# BatteryBoardV2B.net
KiCad netlist of a schematic drawn in EAGLE
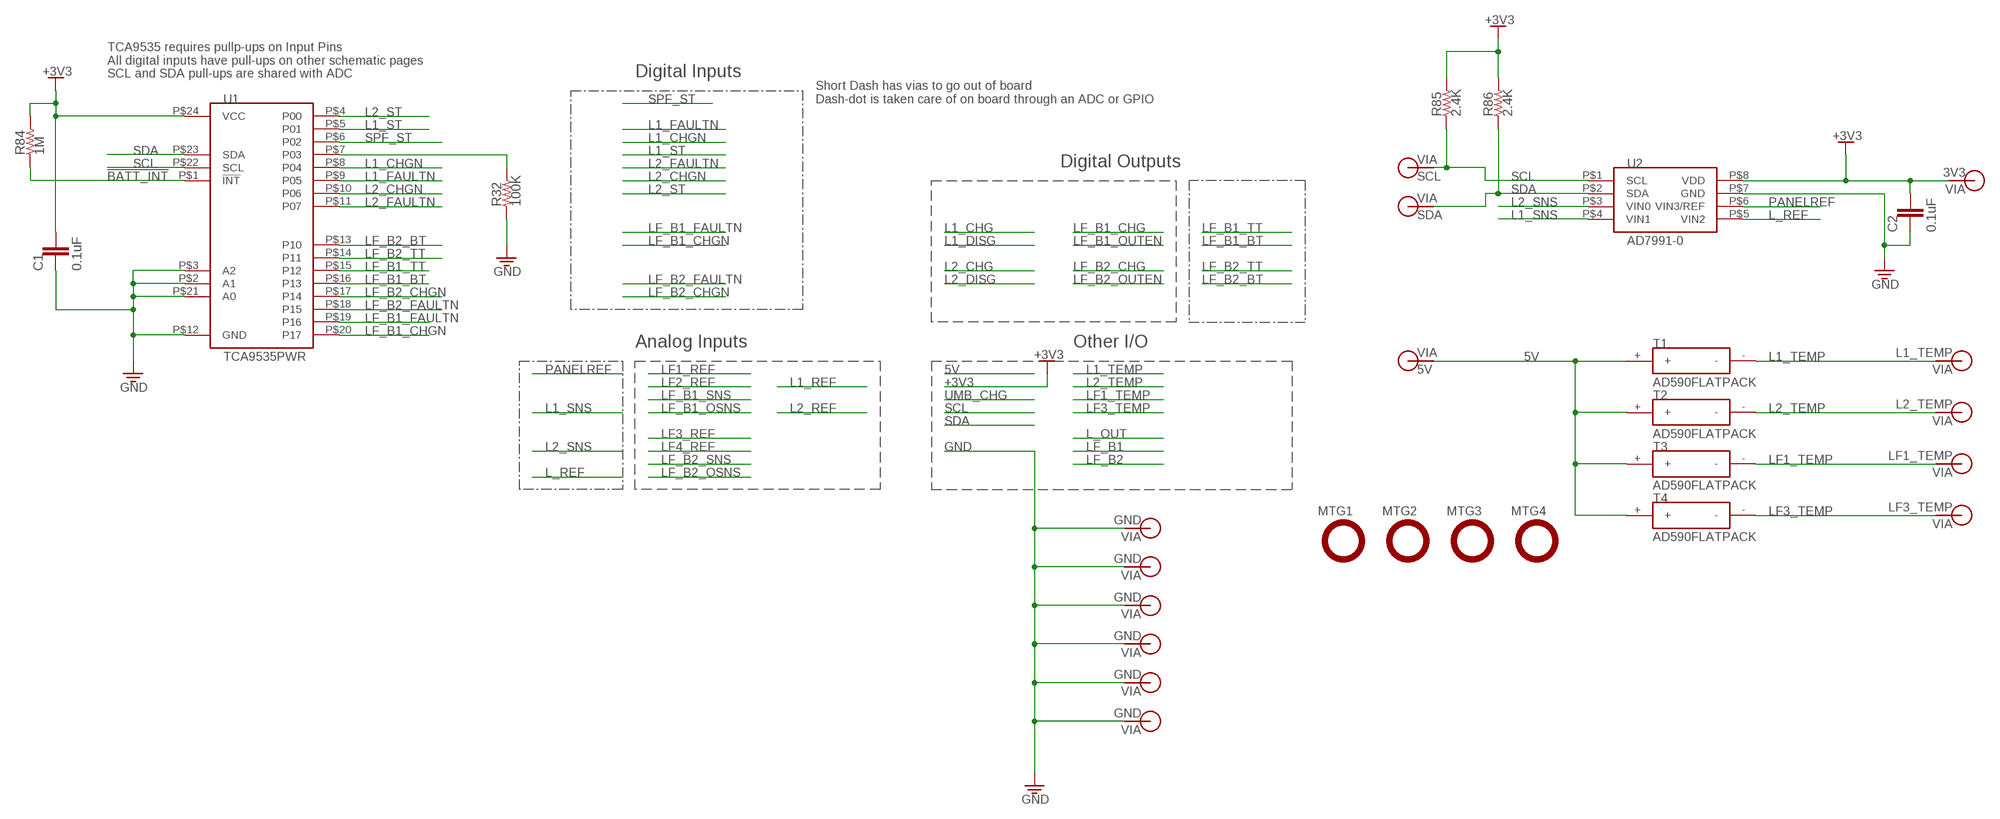
[diagram p0: schematic, sheet 1]
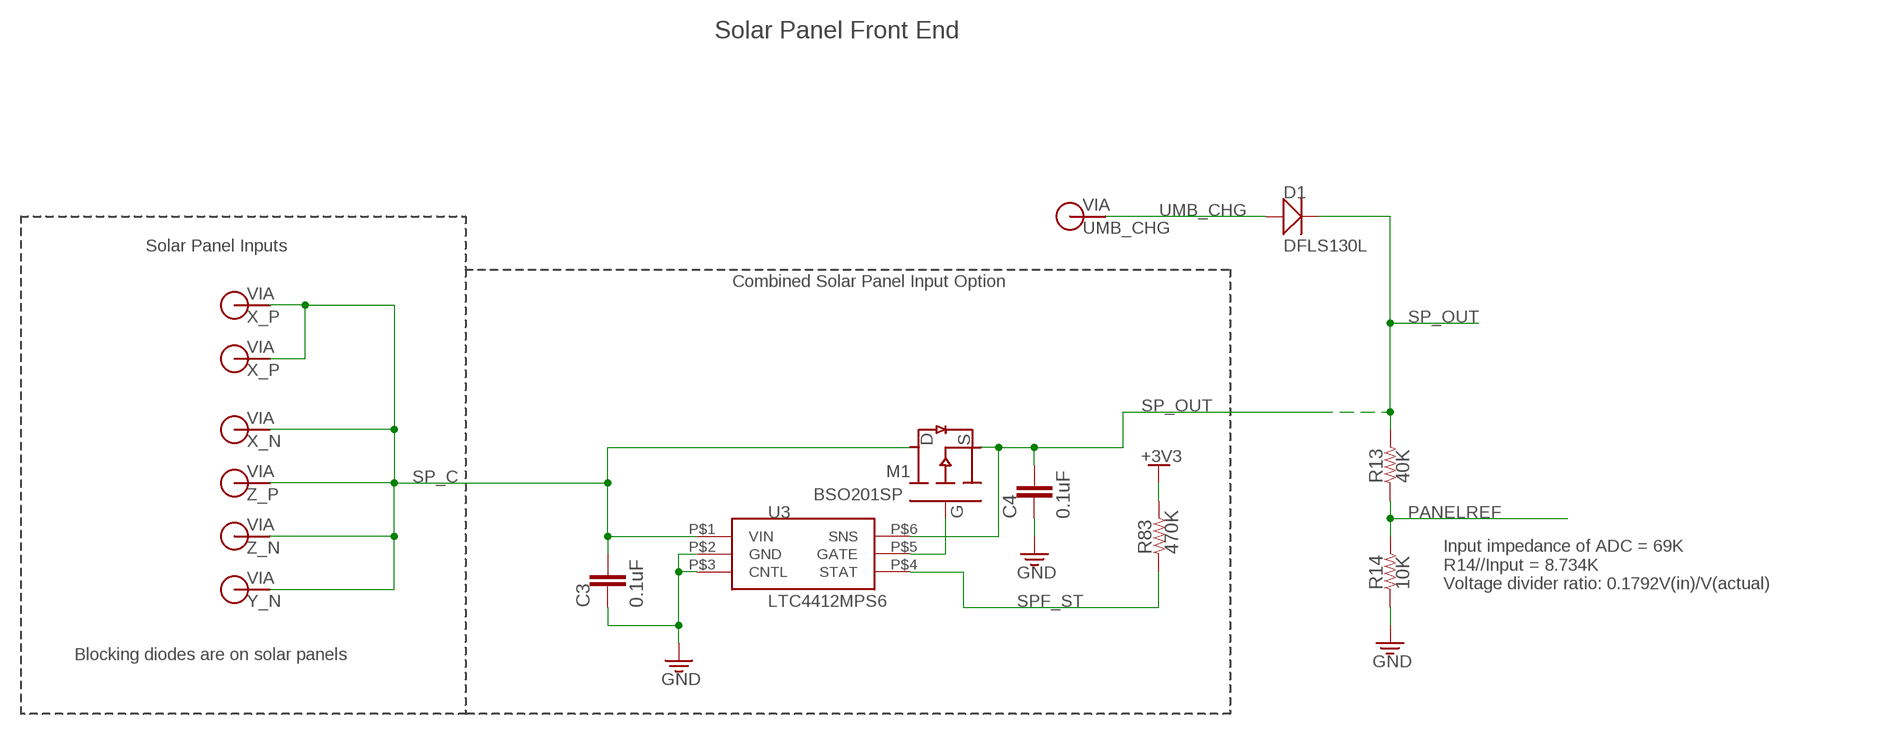
[diagram p1: schematic, sheet 2]
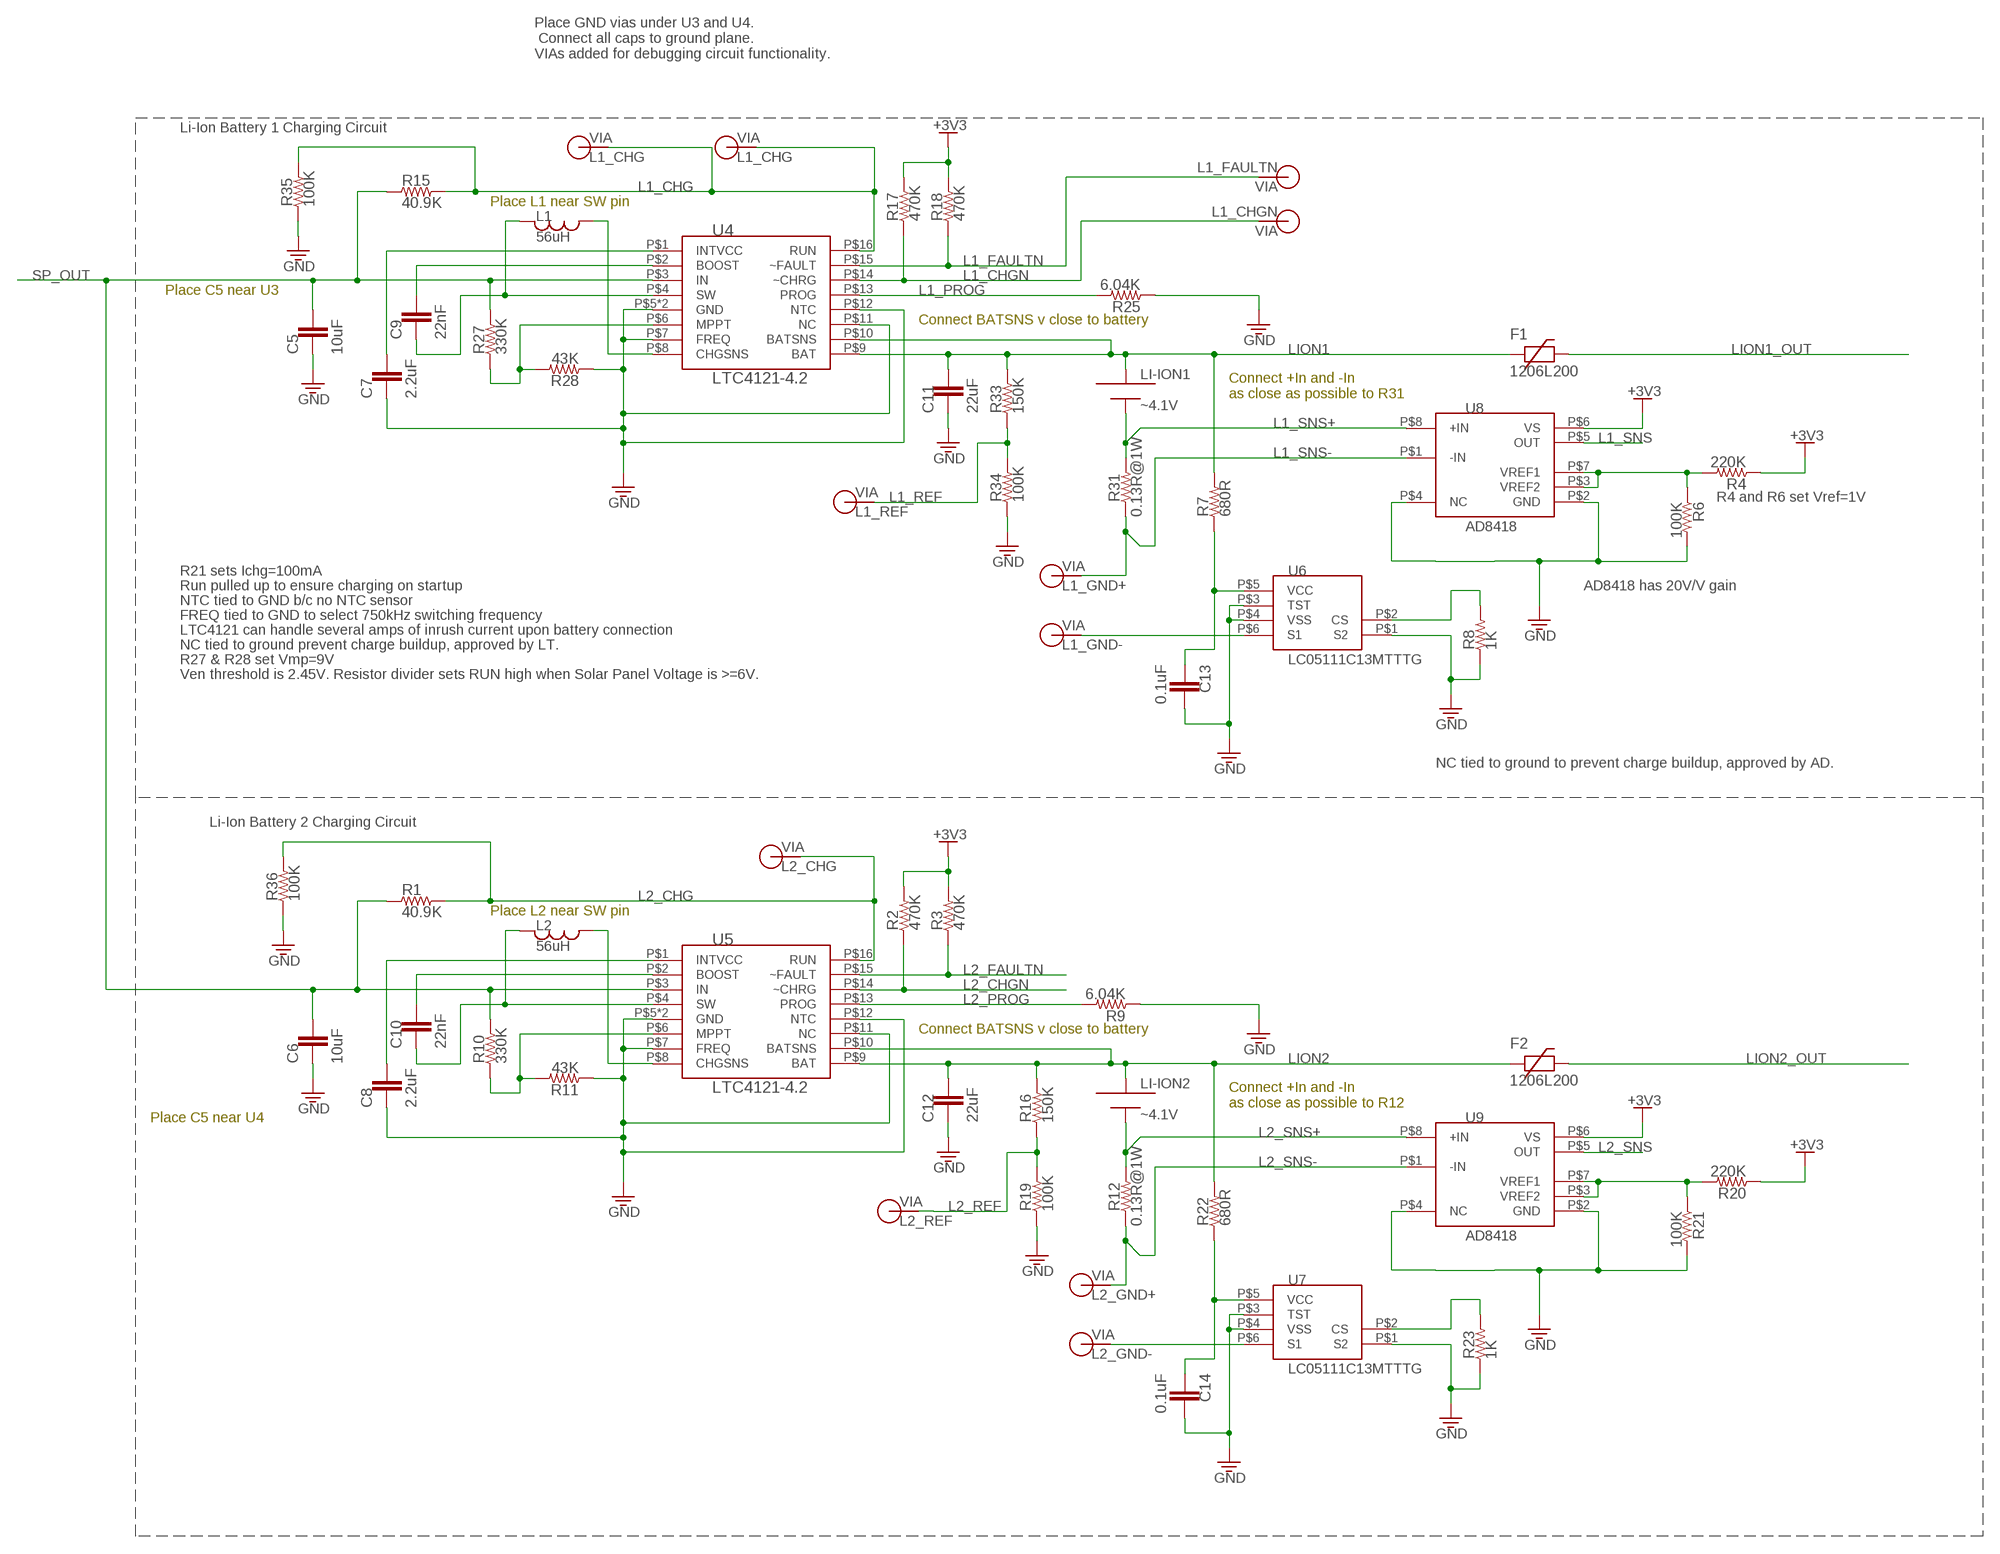
[diagram p2: schematic, sheet 3]
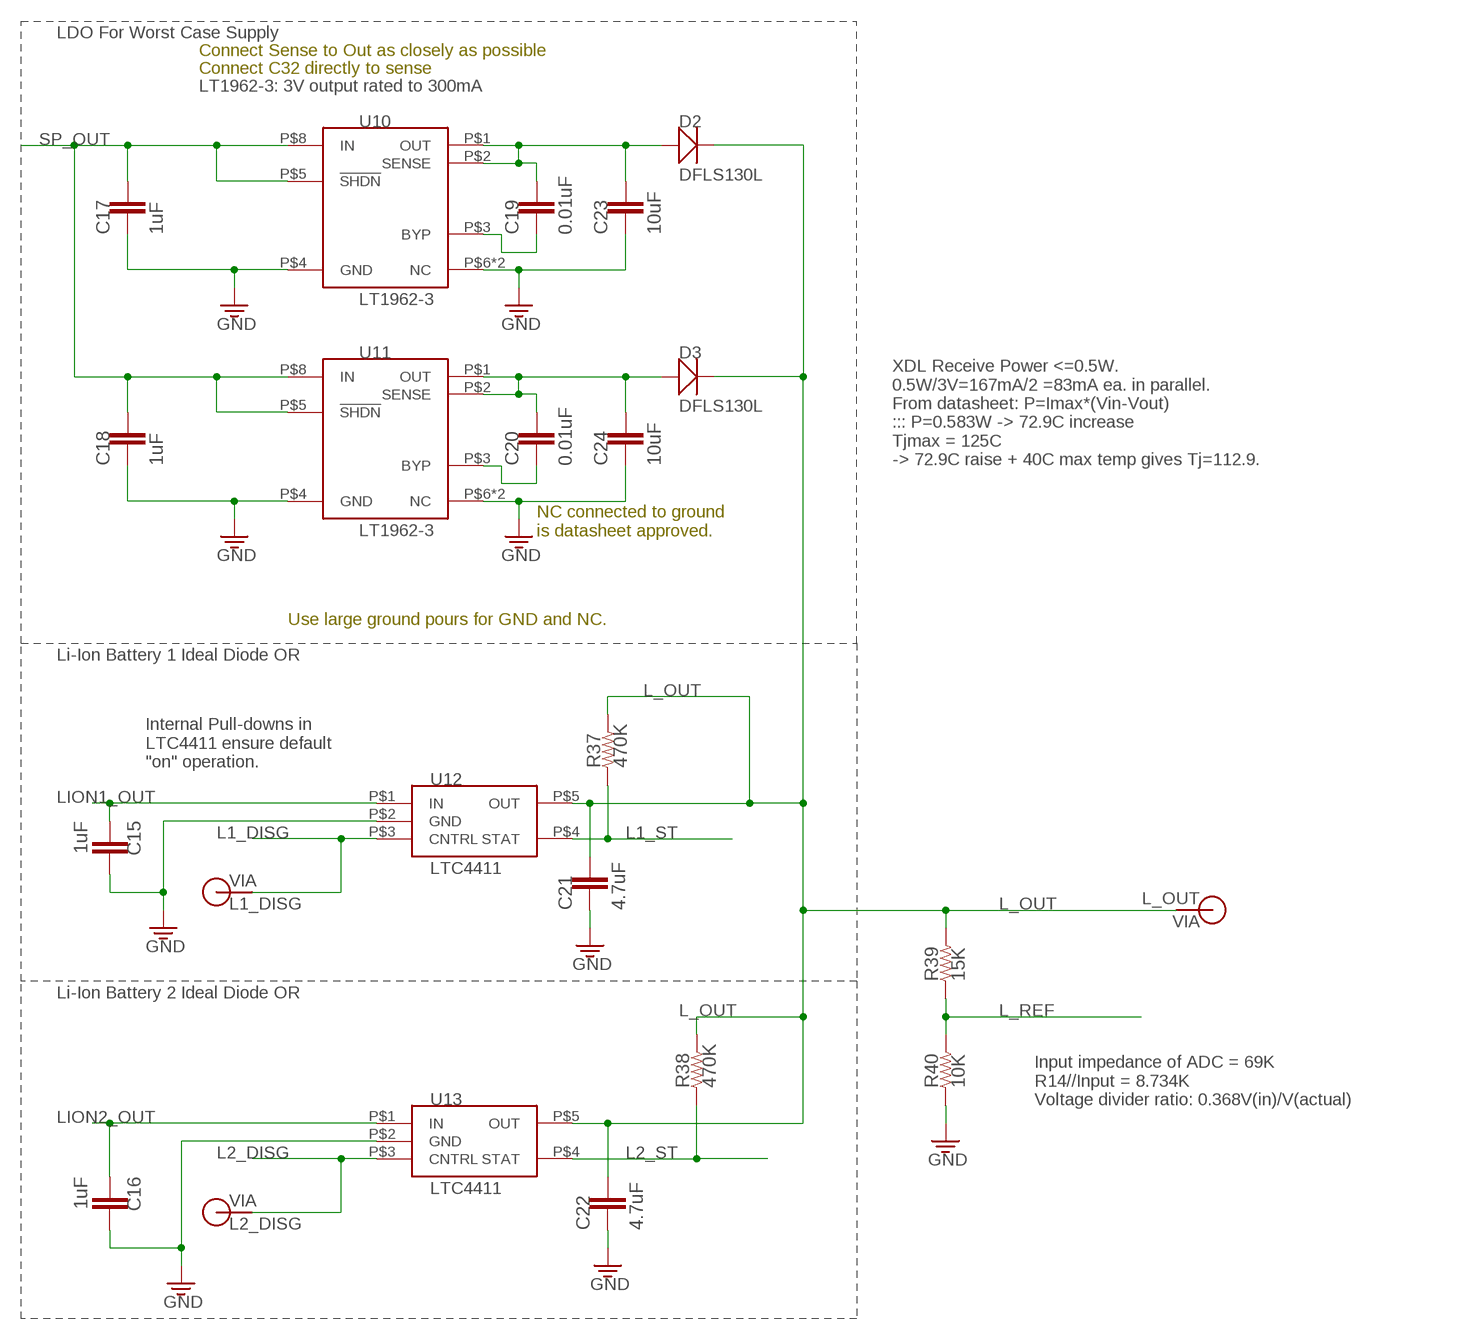
[diagram p3: schematic, sheet 4]
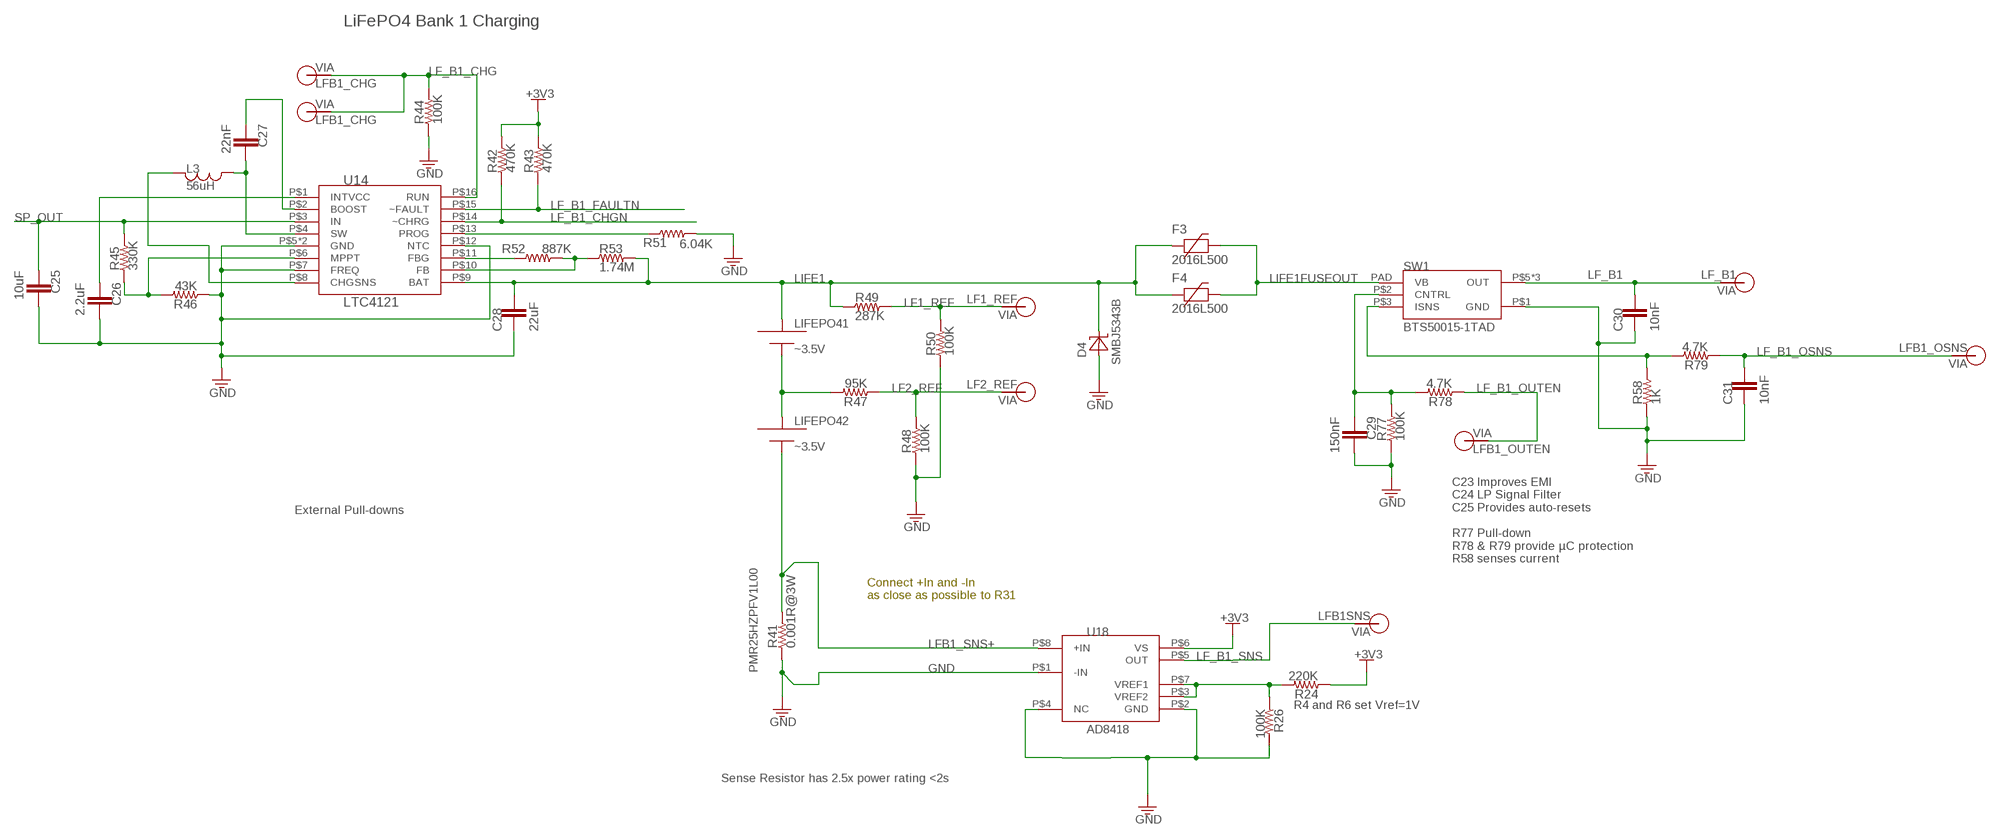
[diagram p4: schematic, sheet 5]
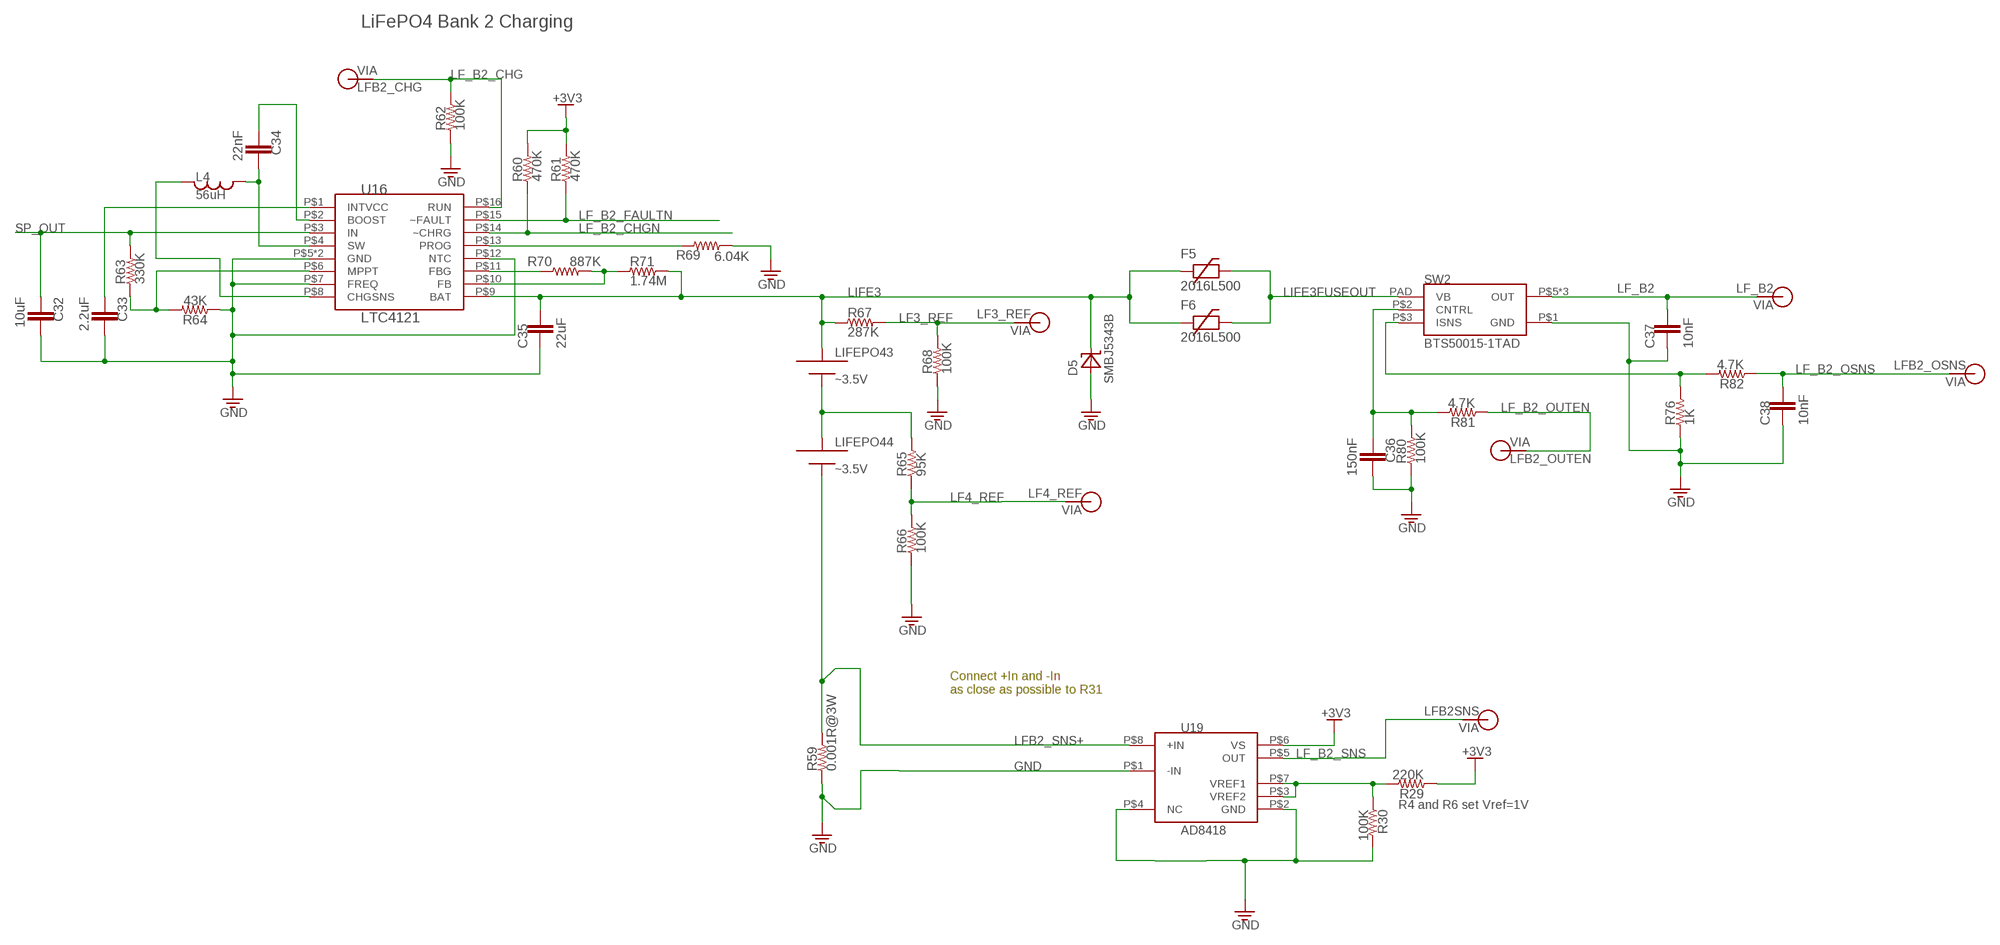
[diagram p5: schematic, sheet 6]

(export (version "E")
  (design (tool "Eeschema 10.0.6"))
  (components
    (comp (ref "C3")
      (value "0.1uF")
      (footprint "eagle-import:0805")
      (libsource (lib "eagle-import") (part "CAP0805"))
    )
    (comp (ref "C4")
      (value "0.1uF")
      (footprint "eagle-import:0805")
      (libsource (lib "eagle-import") (part "CAP0805"))
    )
    (comp (ref "D1")
      (value "DFLS130L")
      (footprint "eagle-import:PWRDI-123")
      (libsource (lib "eagle-import") (part "DFLS130L"))
    )
    (comp (ref "M1")
      (value "BSO201SP")
      (footprint "eagle-import:SO-8")
      (libsource (lib "eagle-import") (part "BSO201SP"))
    )
    (comp (ref "R13")
      (value "40K")
      (footprint "eagle-import:0805")
      (libsource (lib "eagle-import") (part "RES0805"))
    )
    (comp (ref "R14")
      (value "10K")
      (footprint "eagle-import:0805")
      (libsource (lib "eagle-import") (part "RES0805"))
    )
    (comp (ref "R83")
      (value "470K")
      (footprint "eagle-import:0805")
      (libsource (lib "eagle-import") (part "RES0805"))
    )
    (comp (ref "U3")
      (value "LTC4412MPS6")
      (footprint "eagle-import:TSOT23-6")
      (libsource (lib "eagle-import") (part "LTC4412"))
    )
    (comp (ref "V13")
      (value "X_P")
      (footprint "eagle-import:VIA-60MIL")
      (libsource (lib "eagle-import") (part "VIA-60MIL"))
    )
    (comp (ref "V14")
      (value "X_P")
      (footprint "eagle-import:VIA-60MIL-SQ")
      (libsource (lib "eagle-import") (part "VIA60MIL-SQ"))
    )
    (comp (ref "V15")
      (value "X_N")
      (footprint "eagle-import:VIA-60MIL")
      (libsource (lib "eagle-import") (part "VIA-60MIL"))
    )
    (comp (ref "V16")
      (value "Z_P")
      (footprint "eagle-import:VIA-60MIL")
      (libsource (lib "eagle-import") (part "VIA-60MIL"))
    )
    (comp (ref "V17")
      (value "Z_N")
      (footprint "eagle-import:VIA-60MIL")
      (libsource (lib "eagle-import") (part "VIA-60MIL"))
    )
    (comp (ref "V18")
      (value "Y_N")
      (footprint "eagle-import:VIA-60MIL")
      (libsource (lib "eagle-import") (part "VIA-60MIL"))
    )
    (comp (ref "V19")
      (value "UMB_CHG")
      (footprint "eagle-import:VIA-60MIL")
      (libsource (lib "eagle-import") (part "VIA-60MIL"))
    )
    (comp (ref "C1")
      (value "0.1uF")
      (footprint "eagle-import:0805")
      (libsource (lib "eagle-import") (part "CAP0805"))
    )
    (comp (ref "C2")
      (value "0.1uF")
      (footprint "eagle-import:0805")
      (libsource (lib "eagle-import") (part "CAP0805"))
    )
    (comp (ref "MTG1")
      (value "MTG-NPTH-#2-CLOSE")
      (footprint "eagle-import:#2-CLOSE-NPTH")
      (libsource (lib "eagle-import") (part "MTG-NPTH-#2-CLOSE"))
    )
    (comp (ref "MTG2")
      (value "MTG-NPTH-#2-CLOSE")
      (footprint "eagle-import:#2-CLOSE-NPTH")
      (libsource (lib "eagle-import") (part "MTG-NPTH-#2-CLOSE"))
    )
    (comp (ref "MTG3")
      (value "MTG-NPTH-#2-CLOSE")
      (footprint "eagle-import:#2-CLOSE-NPTH")
      (libsource (lib "eagle-import") (part "MTG-NPTH-#2-CLOSE"))
    )
    (comp (ref "MTG4")
      (value "MTG-NPTH-#2-CLOSE")
      (footprint "eagle-import:#2-CLOSE-NPTH")
      (libsource (lib "eagle-import") (part "MTG-NPTH-#2-CLOSE"))
    )
    (comp (ref "R32")
      (value "100K")
      (footprint "eagle-import:0805")
      (libsource (lib "eagle-import") (part "RES0805"))
    )
    (comp (ref "R84")
      (value "1M")
      (footprint "eagle-import:0805")
      (libsource (lib "eagle-import") (part "RES0805"))
    )
    (comp (ref "R85")
      (value "2.4K")
      (footprint "eagle-import:0805")
      (libsource (lib "eagle-import") (part "RES0805"))
    )
    (comp (ref "R86")
      (value "2.4K")
      (footprint "eagle-import:0805")
      (libsource (lib "eagle-import") (part "RES0805"))
    )
    (comp (ref "T1")
      (value "AD590FLATPACK")
      (footprint "eagle-import:FLATPACK")
      (libsource (lib "eagle-import") (part "AD590FLATPACK"))
    )
    (comp (ref "T2")
      (value "AD590FLATPACK")
      (footprint "eagle-import:FLATPACK")
      (libsource (lib "eagle-import") (part "AD590FLATPACK"))
    )
    (comp (ref "T3")
      (value "AD590FLATPACK")
      (footprint "eagle-import:FLATPACK")
      (libsource (lib "eagle-import") (part "AD590FLATPACK"))
    )
    (comp (ref "T4")
      (value "AD590FLATPACK")
      (footprint "eagle-import:FLATPACK")
      (libsource (lib "eagle-import") (part "AD590FLATPACK"))
    )
    (comp (ref "U1")
      (value "TCA9535PWR")
      (footprint "eagle-import:TSSOP-24")
      (libsource (lib "eagle-import") (part "TCA9535PWR"))
    )
    (comp (ref "U2")
      (value "AD7991-0")
      (footprint "eagle-import:SOT-23-8")
      (libsource (lib "eagle-import") (part "AD7991-0"))
    )
    (comp (ref "V1")
      (value "GND")
      (footprint "eagle-import:VIA-120MIL")
      (libsource (lib "eagle-import") (part "VIA-120MIL"))
    )
    (comp (ref "V2")
      (value "GND")
      (footprint "eagle-import:VIA-120MIL")
      (libsource (lib "eagle-import") (part "VIA-120MIL"))
    )
    (comp (ref "V3")
      (value "GND")
      (footprint "eagle-import:VIA-60MIL-SQ")
      (libsource (lib "eagle-import") (part "VIA60MIL-SQ"))
    )
    (comp (ref "V4")
      (value "GND")
      (footprint "eagle-import:VIA-120MIL")
      (libsource (lib "eagle-import") (part "VIA-120MIL"))
    )
    (comp (ref "V5")
      (value "SCL")
      (footprint "eagle-import:VIA-60MIL")
      (libsource (lib "eagle-import") (part "VIA-60MIL"))
    )
    (comp (ref "V6")
      (value "SDA")
      (footprint "eagle-import:VIA-60MIL")
      (libsource (lib "eagle-import") (part "VIA-60MIL"))
    )
    (comp (ref "V7")
      (value "5V")
      (footprint "eagle-import:VIA-60MIL")
      (libsource (lib "eagle-import") (part "VIA-60MIL"))
    )
    (comp (ref "V8")
      (value "L1_TEMP")
      (footprint "eagle-import:VIA-60MIL")
      (libsource (lib "eagle-import") (part "VIA-60MIL"))
    )
    (comp (ref "V9")
      (value "L2_TEMP")
      (footprint "eagle-import:VIA-60MIL")
      (libsource (lib "eagle-import") (part "VIA-60MIL"))
    )
    (comp (ref "V10")
      (value "LF1_TEMP")
      (footprint "eagle-import:VIA-60MIL")
      (libsource (lib "eagle-import") (part "VIA-60MIL"))
    )
    (comp (ref "V11")
      (value "LF3_TEMP")
      (footprint "eagle-import:VIA-60MIL")
      (libsource (lib "eagle-import") (part "VIA-60MIL"))
    )
    (comp (ref "V12")
      (value "3V3")
      (footprint "eagle-import:VIA-60MIL")
      (libsource (lib "eagle-import") (part "VIA-60MIL"))
    )
    (comp (ref "V28")
      (value "GND")
      (footprint "eagle-import:VIA-60MIL-SQ")
      (libsource (lib "eagle-import") (part "VIA60MIL-SQ"))
    )
    (comp (ref "V36")
      (value "GND")
      (footprint "eagle-import:VIA-60MIL-SQ")
      (libsource (lib "eagle-import") (part "VIA60MIL-SQ"))
    )
    (comp (ref "C5")
      (value "10uF")
      (footprint "eagle-import:0805")
      (libsource (lib "eagle-import") (part "CAP0805"))
    )
    (comp (ref "C6")
      (value "10uF")
      (footprint "eagle-import:0805")
      (libsource (lib "eagle-import") (part "CAP0805"))
    )
    (comp (ref "C7")
      (value "2.2uF")
      (footprint "eagle-import:0805")
      (libsource (lib "eagle-import") (part "CAP0805"))
    )
    (comp (ref "C8")
      (value "2.2uF")
      (footprint "eagle-import:0805")
      (libsource (lib "eagle-import") (part "CAP0805"))
    )
    (comp (ref "C9")
      (value "22nF")
      (footprint "eagle-import:0805")
      (libsource (lib "eagle-import") (part "CAP0805"))
    )
    (comp (ref "C10")
      (value "22nF")
      (footprint "eagle-import:0805")
      (libsource (lib "eagle-import") (part "CAP0805"))
    )
    (comp (ref "C11")
      (value "22uF")
      (footprint "eagle-import:0805")
      (libsource (lib "eagle-import") (part "CAP0805"))
    )
    (comp (ref "C12")
      (value "22uF")
      (footprint "eagle-import:0805")
      (libsource (lib "eagle-import") (part "CAP0805"))
    )
    (comp (ref "C13")
      (value "0.1uF")
      (footprint "eagle-import:0805")
      (libsource (lib "eagle-import") (part "CAP0805"))
    )
    (comp (ref "C14")
      (value "0.1uF")
      (footprint "eagle-import:0805")
      (libsource (lib "eagle-import") (part "CAP0805"))
    )
    (comp (ref "F1")
      (value "1206L200")
      (footprint "eagle-import:1206")
      (libsource (lib "eagle-import") (part "PTCFUSE1206"))
    )
    (comp (ref "F2")
      (value "1206L200")
      (footprint "eagle-import:1206")
      (libsource (lib "eagle-import") (part "PTCFUSE1206"))
    )
    (comp (ref "L1")
      (value "56uH")
      (footprint "eagle-import:1812")
      (libsource (lib "eagle-import") (part "IND1812"))
    )
    (comp (ref "L2")
      (value "56uH")
      (footprint "eagle-import:1812")
      (libsource (lib "eagle-import") (part "IND1812"))
    )
    (comp (ref "LI-ION1")
      (value "~4.1V")
      (footprint "eagle-import:EQUISAT-BATTERY-VA")
      (libsource (lib "eagle-import") (part "LI-ION"))
    )
    (comp (ref "LI-ION2")
      (value "~4.1V")
      (footprint "eagle-import:EQUISAT-BATTERY-VA")
      (libsource (lib "eagle-import") (part "LI-ION"))
    )
    (comp (ref "R1")
      (value "40.9K")
      (footprint "eagle-import:0805")
      (libsource (lib "eagle-import") (part "RES0805"))
    )
    (comp (ref "R2")
      (value "470K")
      (footprint "eagle-import:0805")
      (libsource (lib "eagle-import") (part "RES0805"))
    )
    (comp (ref "R3")
      (value "470K")
      (footprint "eagle-import:0805")
      (libsource (lib "eagle-import") (part "RES0805"))
    )
    (comp (ref "R4")
      (value "220K")
      (footprint "eagle-import:0805")
      (libsource (lib "eagle-import") (part "RES0805"))
    )
    (comp (ref "R6")
      (value "100K")
      (footprint "eagle-import:0805")
      (libsource (lib "eagle-import") (part "RES0805"))
    )
    (comp (ref "R7")
      (value "680R")
      (footprint "eagle-import:0805")
      (libsource (lib "eagle-import") (part "RES0805"))
    )
    (comp (ref "R8")
      (value "1K")
      (footprint "eagle-import:0805")
      (libsource (lib "eagle-import") (part "RES0805"))
    )
    (comp (ref "R9")
      (value "6.04K")
      (footprint "eagle-import:0805")
      (libsource (lib "eagle-import") (part "RES0805"))
    )
    (comp (ref "R10")
      (value "330K")
      (footprint "eagle-import:0805")
      (libsource (lib "eagle-import") (part "RES0805"))
    )
    (comp (ref "R11")
      (value "43K")
      (footprint "eagle-import:0805")
      (libsource (lib "eagle-import") (part "RES0805"))
    )
    (comp (ref "R12")
      (value "0.13R@1W")
      (footprint "eagle-import:1210")
      (libsource (lib "eagle-import") (part "RES1210"))
    )
    (comp (ref "R15")
      (value "40.9K")
      (footprint "eagle-import:0805")
      (libsource (lib "eagle-import") (part "RES0805"))
    )
    (comp (ref "R16")
      (value "150K")
      (footprint "eagle-import:0805")
      (libsource (lib "eagle-import") (part "RES0805"))
    )
    (comp (ref "R17")
      (value "470K")
      (footprint "eagle-import:0805")
      (libsource (lib "eagle-import") (part "RES0805"))
    )
    (comp (ref "R18")
      (value "470K")
      (footprint "eagle-import:0805")
      (libsource (lib "eagle-import") (part "RES0805"))
    )
    (comp (ref "R19")
      (value "100K")
      (footprint "eagle-import:0805")
      (libsource (lib "eagle-import") (part "RES0805"))
    )
    (comp (ref "R20")
      (value "220K")
      (footprint "eagle-import:0805")
      (libsource (lib "eagle-import") (part "RES0805"))
    )
    (comp (ref "R21")
      (value "100K")
      (footprint "eagle-import:0805")
      (libsource (lib "eagle-import") (part "RES0805"))
    )
    (comp (ref "R22")
      (value "680R")
      (footprint "eagle-import:0805")
      (libsource (lib "eagle-import") (part "RES0805"))
    )
    (comp (ref "R23")
      (value "1K")
      (footprint "eagle-import:0805")
      (libsource (lib "eagle-import") (part "RES0805"))
    )
    (comp (ref "R25")
      (value "6.04K")
      (footprint "eagle-import:0805")
      (libsource (lib "eagle-import") (part "RES0805"))
    )
    (comp (ref "R27")
      (value "330K")
      (footprint "eagle-import:0805")
      (libsource (lib "eagle-import") (part "RES0805"))
    )
    (comp (ref "R28")
      (value "43K")
      (footprint "eagle-import:0805")
      (libsource (lib "eagle-import") (part "RES0805"))
    )
    (comp (ref "R31")
      (value "0.13R@1W")
      (footprint "eagle-import:1210")
      (libsource (lib "eagle-import") (part "RES1210"))
    )
    (comp (ref "R33")
      (value "150K")
      (footprint "eagle-import:0805")
      (libsource (lib "eagle-import") (part "RES0805"))
    )
    (comp (ref "R34")
      (value "100K")
      (footprint "eagle-import:0805")
      (libsource (lib "eagle-import") (part "RES0805"))
    )
    (comp (ref "R35")
      (value "100K")
      (footprint "eagle-import:0805")
      (libsource (lib "eagle-import") (part "RES0805"))
    )
    (comp (ref "R36")
      (value "100K")
      (footprint "eagle-import:0805")
      (libsource (lib "eagle-import") (part "RES0805"))
    )
    (comp (ref "U4")
      (value "LTC4121-4.2")
      (footprint "eagle-import:QFN-16-PAD")
      (libsource (lib "eagle-import") (part "LTC4121-4.2"))
    )
    (comp (ref "U5")
      (value "LTC4121-4.2")
      (footprint "eagle-import:QFN-16-PAD")
      (libsource (lib "eagle-import") (part "LTC4121-4.2"))
    )
    (comp (ref "U6")
      (value "LC05111C13MTTTG")
      (footprint "eagle-import:WDFN6")
      (libsource (lib "eagle-import") (part "LC05111C13MTTTG"))
    )
    (comp (ref "U7")
      (value "LC05111C13MTTTG")
      (footprint "eagle-import:WDFN6")
      (libsource (lib "eagle-import") (part "LC05111C13MTTTG"))
    )
    (comp (ref "U8")
      (value "AD8418")
      (footprint "eagle-import:MSOP-8")
      (libsource (lib "eagle-import") (part "AD8418"))
    )
    (comp (ref "U9")
      (value "AD8418")
      (footprint "eagle-import:MSOP-8")
      (libsource (lib "eagle-import") (part "AD8418"))
    )
    (comp (ref "V20")
      (value "L1_CHG")
      (footprint "eagle-import:VIA-60MIL")
      (libsource (lib "eagle-import") (part "VIA-60MIL"))
    )
    (comp (ref "V21")
      (value "L1_REF")
      (footprint "eagle-import:VIA-60MIL")
      (libsource (lib "eagle-import") (part "VIA-60MIL"))
    )
    (comp (ref "V22")
      (value "L1_GND+")
      (footprint "eagle-import:VIA-60MIL")
      (libsource (lib "eagle-import") (part "VIA-60MIL"))
    )
    (comp (ref "V23")
      (value "L1_GND-")
      (footprint "eagle-import:VIA-60MIL")
      (libsource (lib "eagle-import") (part "VIA-60MIL"))
    )
    (comp (ref "V24")
      (value "L2_GND+")
      (footprint "eagle-import:VIA-60MIL")
      (libsource (lib "eagle-import") (part "VIA-60MIL"))
    )
    (comp (ref "V25")
      (value "L2_GND-")
      (footprint "eagle-import:VIA-60MIL")
      (libsource (lib "eagle-import") (part "VIA-60MIL"))
    )
    (comp (ref "V26")
      (value "L1_FAULTN")
      (footprint "eagle-import:VIA-60MIL-SQ")
      (libsource (lib "eagle-import") (part "VIA60MIL-SQ"))
    )
    (comp (ref "V27")
      (value "L1_CHGN")
      (footprint "eagle-import:VIA-60MIL-SQ")
      (libsource (lib "eagle-import") (part "VIA60MIL-SQ"))
    )
    (comp (ref "V31")
      (value "L2_REF")
      (footprint "eagle-import:VIA-60MIL")
      (libsource (lib "eagle-import") (part "VIA-60MIL"))
    )
    (comp (ref "V33")
      (value "L2_CHG")
      (footprint "eagle-import:VIA-60MIL")
      (libsource (lib "eagle-import") (part "VIA-60MIL"))
    )
    (comp (ref "V48")
      (value "L1_CHG")
      (footprint "eagle-import:VIA-60MIL-SQ")
      (libsource (lib "eagle-import") (part "VIA60MIL-SQ"))
    )
    (comp (ref "C15")
      (value "1uF")
      (footprint "eagle-import:0805")
      (libsource (lib "eagle-import") (part "CAP0805"))
    )
    (comp (ref "C16")
      (value "1uF")
      (footprint "eagle-import:0805")
      (libsource (lib "eagle-import") (part "CAP0805"))
    )
    (comp (ref "C17")
      (value "1uF")
      (footprint "eagle-import:0805")
      (libsource (lib "eagle-import") (part "CAP0805"))
    )
    (comp (ref "C18")
      (value "1uF")
      (footprint "eagle-import:0805")
      (libsource (lib "eagle-import") (part "CAP0805"))
    )
    (comp (ref "C19")
      (value "0.01uF")
      (footprint "eagle-import:0805")
      (libsource (lib "eagle-import") (part "CAP0805"))
    )
    (comp (ref "C20")
      (value "0.01uF")
      (footprint "eagle-import:0805")
      (libsource (lib "eagle-import") (part "CAP0805"))
    )
    (comp (ref "C21")
      (value "4.7uF")
      (footprint "eagle-import:0805")
      (libsource (lib "eagle-import") (part "CAP0805"))
    )
    (comp (ref "C22")
      (value "4.7uF")
      (footprint "eagle-import:0805")
      (libsource (lib "eagle-import") (part "CAP0805"))
    )
    (comp (ref "C23")
      (value "10uF")
      (footprint "eagle-import:0805")
      (libsource (lib "eagle-import") (part "CAP0805"))
    )
    (comp (ref "C24")
      (value "10uF")
      (footprint "eagle-import:0805")
      (libsource (lib "eagle-import") (part "CAP0805"))
    )
    (comp (ref "D2")
      (value "DFLS130L")
      (footprint "eagle-import:PWRDI-123")
      (libsource (lib "eagle-import") (part "DFLS130L"))
    )
    (comp (ref "D3")
      (value "DFLS130L")
      (footprint "eagle-import:PWRDI-123")
      (libsource (lib "eagle-import") (part "DFLS130L"))
    )
    (comp (ref "R37")
      (value "470K")
      (footprint "eagle-import:0805")
      (libsource (lib "eagle-import") (part "RES0805"))
    )
    (comp (ref "R38")
      (value "470K")
      (footprint "eagle-import:0805")
      (libsource (lib "eagle-import") (part "RES0805"))
    )
    (comp (ref "R39")
      (value "15K")
      (footprint "eagle-import:0805")
      (libsource (lib "eagle-import") (part "RES0805"))
    )
    (comp (ref "R40")
      (value "10K")
      (footprint "eagle-import:0805")
      (libsource (lib "eagle-import") (part "RES0805"))
    )
    (comp (ref "U10")
      (value "LT1962-3")
      (footprint "eagle-import:MSOP-8")
      (libsource (lib "eagle-import") (part "LT1962-3"))
    )
    (comp (ref "U11")
      (value "LT1962-3")
      (footprint "eagle-import:MSOP-8")
      (libsource (lib "eagle-import") (part "LT1962-3"))
    )
    (comp (ref "U12")
      (value "LTC4411")
      (footprint "eagle-import:TSOT23-5")
      (libsource (lib "eagle-import") (part "LTC4411"))
    )
    (comp (ref "U13")
      (value "LTC4411")
      (footprint "eagle-import:TSOT23-5")
      (libsource (lib "eagle-import") (part "LTC4411"))
    )
    (comp (ref "V29")
      (value "L1_DISG")
      (footprint "eagle-import:VIA-60MIL")
      (libsource (lib "eagle-import") (part "VIA-60MIL"))
    )
    (comp (ref "V30")
      (value "L2_DISG")
      (footprint "eagle-import:VIA-60MIL")
      (libsource (lib "eagle-import") (part "VIA-60MIL"))
    )
    (comp (ref "V34")
      (value "L_OUT")
      (footprint "eagle-import:VIA-120MIL")
      (libsource (lib "eagle-import") (part "VIA-120MIL"))
    )
    (comp (ref "C25")
      (value "10uF")
      (footprint "eagle-import:0805")
      (libsource (lib "eagle-import") (part "CAP0805"))
    )
    (comp (ref "C26")
      (value "2.2uF")
      (footprint "eagle-import:0805")
      (libsource (lib "eagle-import") (part "CAP0805"))
    )
    (comp (ref "C27")
      (value "22nF")
      (footprint "eagle-import:0805")
      (libsource (lib "eagle-import") (part "CAP0805"))
    )
    (comp (ref "C28")
      (value "22uF")
      (footprint "eagle-import:0805")
      (libsource (lib "eagle-import") (part "CAP0805"))
    )
    (comp (ref "C29")
      (value "150nF")
      (footprint "eagle-import:0805")
      (libsource (lib "eagle-import") (part "CAP0805"))
    )
    (comp (ref "C30")
      (value "10nF")
      (footprint "eagle-import:0805")
      (libsource (lib "eagle-import") (part "CAP0805"))
    )
    (comp (ref "C31")
      (value "10nF")
      (footprint "eagle-import:0805")
      (libsource (lib "eagle-import") (part "CAP0805"))
    )
    (comp (ref "D4")
      (value "SMBJ5343B")
      (footprint "eagle-import:DO214AA")
      (libsource (lib "eagle-import") (part "SMBJ5343B"))
    )
    (comp (ref "F3")
      (value "2016L500")
      (footprint "eagle-import:2016")
      (libsource (lib "eagle-import") (part "2016L500"))
    )
    (comp (ref "F4")
      (value "2016L500")
      (footprint "eagle-import:2016")
      (libsource (lib "eagle-import") (part "2016L500"))
    )
    (comp (ref "L3")
      (value "56uH")
      (footprint "eagle-import:1812")
      (libsource (lib "eagle-import") (part "IND1812"))
    )
    (comp (ref "LIFEPO41")
      (value "~3.5V")
      (footprint "eagle-import:EQUISAT-BATTERY-VA")
      (libsource (lib "eagle-import") (part "LIFEPO4VA"))
    )
    (comp (ref "LIFEPO42")
      (value "~3.5V")
      (footprint "eagle-import:EQUISAT-BATTERY-VB")
      (libsource (lib "eagle-import") (part "LIFEPO4VB"))
    )
    (comp (ref "R24")
      (value "220K")
      (footprint "eagle-import:0805")
      (libsource (lib "eagle-import") (part "RES0805"))
    )
    (comp (ref "R26")
      (value "100K")
      (footprint "eagle-import:0805")
      (libsource (lib "eagle-import") (part "RES0805"))
    )
    (comp (ref "R41")
      (value "0.001R@3W")
      (footprint "eagle-import:1210")
      (libsource (lib "eagle-import") (part "RES1210"))
    )
    (comp (ref "R42")
      (value "470K")
      (footprint "eagle-import:0805")
      (libsource (lib "eagle-import") (part "RES0805"))
    )
    (comp (ref "R43")
      (value "470K")
      (footprint "eagle-import:0805")
      (libsource (lib "eagle-import") (part "RES0805"))
    )
    (comp (ref "R44")
      (value "100K")
      (footprint "eagle-import:0805")
      (libsource (lib "eagle-import") (part "RES0805"))
    )
    (comp (ref "R45")
      (value "330K")
      (footprint "eagle-import:0805")
      (libsource (lib "eagle-import") (part "RES0805"))
    )
    (comp (ref "R46")
      (value "43K")
      (footprint "eagle-import:0805")
      (libsource (lib "eagle-import") (part "RES0805"))
    )
    (comp (ref "R47")
      (value "95K")
      (footprint "eagle-import:0805")
      (libsource (lib "eagle-import") (part "RES0805"))
    )
    (comp (ref "R48")
      (value "100K")
      (footprint "eagle-import:0805")
      (libsource (lib "eagle-import") (part "RES0805"))
    )
    (comp (ref "R49")
      (value "287K")
      (footprint "eagle-import:0805")
      (libsource (lib "eagle-import") (part "RES0805"))
    )
    (comp (ref "R50")
      (value "100K")
      (footprint "eagle-import:0805")
      (libsource (lib "eagle-import") (part "RES0805"))
    )
    (comp (ref "R51")
      (value "6.04K")
      (footprint "eagle-import:0805")
      (libsource (lib "eagle-import") (part "RES0805"))
    )
    (comp (ref "R52")
      (value "887K")
      (footprint "eagle-import:0805")
      (libsource (lib "eagle-import") (part "RES0805"))
    )
    (comp (ref "R53")
      (value "1.74M")
      (footprint "eagle-import:0805")
      (libsource (lib "eagle-import") (part "RES0805"))
    )
    (comp (ref "R58")
      (value "1K")
      (footprint "eagle-import:0805")
      (libsource (lib "eagle-import") (part "RES0805"))
    )
    (comp (ref "R77")
      (value "100K")
      (footprint "eagle-import:0805")
      (libsource (lib "eagle-import") (part "RES0805"))
    )
    (comp (ref "R78")
      (value "4.7K")
      (footprint "eagle-import:0805")
      (libsource (lib "eagle-import") (part "RES0805"))
    )
    (comp (ref "R79")
      (value "4.7K")
      (footprint "eagle-import:0805")
      (libsource (lib "eagle-import") (part "RES0805"))
    )
    (comp (ref "SW1")
      (value "BTS50015-1TAD")
      (footprint "eagle-import:TO-263-7-8")
      (libsource (lib "eagle-import") (part "BTS50015-1TAD"))
    )
    (comp (ref "U14")
      (value "LTC4121")
      (footprint "eagle-import:QFN-16-PAD")
      (libsource (lib "eagle-import") (part "LTC4121"))
    )
    (comp (ref "U18")
      (value "AD8418")
      (footprint "eagle-import:MSOP-8")
      (libsource (lib "eagle-import") (part "AD8418"))
    )
    (comp (ref "V32")
      (value "LFB1_CHG")
      (footprint "eagle-import:VIA-60MIL-SQ")
      (libsource (lib "eagle-import") (part "VIA60MIL-SQ"))
    )
    (comp (ref "V35")
      (value "LFB1_CHG")
      (footprint "eagle-import:VIA-60MIL")
      (libsource (lib "eagle-import") (part "VIA-60MIL"))
    )
    (comp (ref "V40")
      (value "LFB1SNS")
      (footprint "eagle-import:VIA-60MIL")
      (libsource (lib "eagle-import") (part "VIA-60MIL"))
    )
    (comp (ref "V41")
      (value "LF1_REF")
      (footprint "eagle-import:VIA-60MIL")
      (libsource (lib "eagle-import") (part "VIA-60MIL"))
    )
    (comp (ref "V42")
      (value "LF2_REF")
      (footprint "eagle-import:VIA-60MIL")
      (libsource (lib "eagle-import") (part "VIA-60MIL"))
    )
    (comp (ref "V43")
      (value "LFB1_OUTEN")
      (footprint "eagle-import:VIA-60MIL")
      (libsource (lib "eagle-import") (part "VIA-60MIL"))
    )
    (comp (ref "V45")
      (value "LF_B1")
      (footprint "eagle-import:VIA-120MIL")
      (libsource (lib "eagle-import") (part "VIA-120MIL"))
    )
    (comp (ref "V46")
      (value "LFB1_OSNS")
      (footprint "eagle-import:VIA-60MIL")
      (libsource (lib "eagle-import") (part "VIA-60MIL"))
    )
    (comp (ref "C32")
      (value "10uF")
      (footprint "eagle-import:0805")
      (libsource (lib "eagle-import") (part "CAP0805"))
    )
    (comp (ref "C33")
      (value "2.2uF")
      (footprint "eagle-import:0805")
      (libsource (lib "eagle-import") (part "CAP0805"))
    )
    (comp (ref "C34")
      (value "22nF")
      (footprint "eagle-import:0805")
      (libsource (lib "eagle-import") (part "CAP0805"))
    )
    (comp (ref "C35")
      (value "22uF")
      (footprint "eagle-import:0805")
      (libsource (lib "eagle-import") (part "CAP0805"))
    )
    (comp (ref "C36")
      (value "150nF")
      (footprint "eagle-import:0805")
      (libsource (lib "eagle-import") (part "CAP0805"))
    )
    (comp (ref "C37")
      (value "10nF")
      (footprint "eagle-import:0805")
      (libsource (lib "eagle-import") (part "CAP0805"))
    )
    (comp (ref "C38")
      (value "10nF")
      (footprint "eagle-import:0805")
      (libsource (lib "eagle-import") (part "CAP0805"))
    )
    (comp (ref "D5")
      (value "SMBJ5343B")
      (footprint "eagle-import:DO214AA")
      (libsource (lib "eagle-import") (part "SMBJ5343B"))
    )
    (comp (ref "F5")
      (value "2016L500")
      (footprint "eagle-import:2016")
      (libsource (lib "eagle-import") (part "2016L500"))
    )
    (comp (ref "F6")
      (value "2016L500")
      (footprint "eagle-import:2016")
      (libsource (lib "eagle-import") (part "2016L500"))
    )
    (comp (ref "L4")
      (value "56uH")
      (footprint "eagle-import:1812")
      (libsource (lib "eagle-import") (part "IND1812"))
    )
    (comp (ref "LIFEPO43")
      (value "~3.5V")
      (footprint "eagle-import:EQUISAT-BATTERY-VA")
      (libsource (lib "eagle-import") (part "LIFEPO4VA"))
    )
    (comp (ref "LIFEPO44")
      (value "~3.5V")
      (footprint "eagle-import:EQUISAT-BATTERY-VB")
      (libsource (lib "eagle-import") (part "LIFEPO4VB"))
    )
    (comp (ref "R29")
      (value "220K")
      (footprint "eagle-import:0805")
      (libsource (lib "eagle-import") (part "RES0805"))
    )
    (comp (ref "R30")
      (value "100K")
      (footprint "eagle-import:0805")
      (libsource (lib "eagle-import") (part "RES0805"))
    )
    (comp (ref "R59")
      (value "0.001R@3W")
      (footprint "eagle-import:1210")
      (libsource (lib "eagle-import") (part "RES1210"))
    )
    (comp (ref "R60")
      (value "470K")
      (footprint "eagle-import:0805")
      (libsource (lib "eagle-import") (part "RES0805"))
    )
    (comp (ref "R61")
      (value "470K")
      (footprint "eagle-import:0805")
      (libsource (lib "eagle-import") (part "RES0805"))
    )
    (comp (ref "R62")
      (value "100K")
      (footprint "eagle-import:0805")
      (libsource (lib "eagle-import") (part "RES0805"))
    )
    (comp (ref "R63")
      (value "330K")
      (footprint "eagle-import:0805")
      (libsource (lib "eagle-import") (part "RES0805"))
    )
    (comp (ref "R64")
      (value "43K")
      (footprint "eagle-import:0805")
      (libsource (lib "eagle-import") (part "RES0805"))
    )
    (comp (ref "R65")
      (value "95K")
      (footprint "eagle-import:0805")
      (libsource (lib "eagle-import") (part "RES0805"))
    )
    (comp (ref "R66")
      (value "100K")
      (footprint "eagle-import:0805")
      (libsource (lib "eagle-import") (part "RES0805"))
    )
    (comp (ref "R67")
      (value "287K")
      (footprint "eagle-import:0805")
      (libsource (lib "eagle-import") (part "RES0805"))
    )
    (comp (ref "R68")
      (value "100K")
      (footprint "eagle-import:0805")
      (libsource (lib "eagle-import") (part "RES0805"))
    )
    (comp (ref "R69")
      (value "6.04K")
      (footprint "eagle-import:0805")
      (libsource (lib "eagle-import") (part "RES0805"))
    )
    (comp (ref "R70")
      (value "887K")
      (footprint "eagle-import:0805")
      (libsource (lib "eagle-import") (part "RES0805"))
    )
    (comp (ref "R71")
      (value "1.74M")
      (footprint "eagle-import:0805")
      (libsource (lib "eagle-import") (part "RES0805"))
    )
    (comp (ref "R76")
      (value "1K")
      (footprint "eagle-import:0805")
      (libsource (lib "eagle-import") (part "RES0805"))
    )
    (comp (ref "R80")
      (value "100K")
      (footprint "eagle-import:0805")
      (libsource (lib "eagle-import") (part "RES0805"))
    )
    (comp (ref "R81")
      (value "4.7K")
      (footprint "eagle-import:0805")
      (libsource (lib "eagle-import") (part "RES0805"))
    )
    (comp (ref "R82")
      (value "4.7K")
      (footprint "eagle-import:0805")
      (libsource (lib "eagle-import") (part "RES0805"))
    )
    (comp (ref "SW2")
      (value "BTS50015-1TAD")
      (footprint "eagle-import:TO-263-7-8")
      (libsource (lib "eagle-import") (part "BTS50015-1TAD"))
    )
    (comp (ref "U16")
      (value "LTC4121")
      (footprint "eagle-import:QFN-16-PAD")
      (libsource (lib "eagle-import") (part "LTC4121"))
    )
    (comp (ref "U19")
      (value "AD8418")
      (footprint "eagle-import:MSOP-8")
      (libsource (lib "eagle-import") (part "AD8418"))
    )
    (comp (ref "V44")
      (value "LFB2SNS")
      (footprint "eagle-import:VIA-60MIL")
      (libsource (lib "eagle-import") (part "VIA-60MIL"))
    )
    (comp (ref "V47")
      (value "LFB2_CHG")
      (footprint "eagle-import:VIA-60MIL")
      (libsource (lib "eagle-import") (part "VIA-60MIL"))
    )
    (comp (ref "V49")
      (value "LF3_REF")
      (footprint "eagle-import:VIA-60MIL")
      (libsource (lib "eagle-import") (part "VIA-60MIL"))
    )
    (comp (ref "V50")
      (value "LF4_REF")
      (footprint "eagle-import:VIA-60MIL")
      (libsource (lib "eagle-import") (part "VIA-60MIL"))
    )
    (comp (ref "V51")
      (value "LFB2_OUTEN")
      (footprint "eagle-import:VIA-60MIL")
      (libsource (lib "eagle-import") (part "VIA-60MIL"))
    )
    (comp (ref "V53")
      (value "LF_B2")
      (footprint "eagle-import:VIA-120MIL")
      (libsource (lib "eagle-import") (part "VIA-120MIL"))
    )
    (comp (ref "V99")
      (value "LFB2_OSNS")
      (footprint "eagle-import:VIA-60MIL")
      (libsource (lib "eagle-import") (part "VIA-60MIL"))
    )
  )
  (nets
    (net (code "1") (name "+3V3") (class "Default")
      (node (ref "C1") (pin "1") (pinfunction "P$1_1") (pintype "passive"))
      (node (ref "C2") (pin "1") (pinfunction "P$1_1") (pintype "passive"))
      (node (ref "R17") (pin "2") (pinfunction "2_2") (pintype "passive"))
      (node (ref "R18") (pin "2") (pinfunction "2_2") (pintype "passive"))
      (node (ref "R2") (pin "2") (pinfunction "2_2") (pintype "passive"))
      (node (ref "R20") (pin "1") (pinfunction "1_1") (pintype "passive"))
      (node (ref "R24") (pin "1") (pinfunction "1_1") (pintype "passive"))
      (node (ref "R29") (pin "1") (pinfunction "1_1") (pintype "passive"))
      (node (ref "R3") (pin "2") (pinfunction "2_2") (pintype "passive"))
      (node (ref "R4") (pin "1") (pinfunction "1_1") (pintype "passive"))
      (node (ref "R42") (pin "2") (pinfunction "2_2") (pintype "passive"))
      (node (ref "R43") (pin "2") (pinfunction "2_2") (pintype "passive"))
      (node (ref "R60") (pin "2") (pinfunction "2_2") (pintype "passive"))
      (node (ref "R61") (pin "2") (pinfunction "2_2") (pintype "passive"))
      (node (ref "R83") (pin "2") (pinfunction "2_2") (pintype "passive"))
      (node (ref "R84") (pin "2") (pinfunction "2_2") (pintype "passive"))
      (node (ref "R85") (pin "2") (pinfunction "2_2") (pintype "passive"))
      (node (ref "R86") (pin "2") (pinfunction "2_2") (pintype "passive"))
      (node (ref "U1") (pin "P$24") (pinfunction "VCC_P$24") (pintype "power_in"))
      (node (ref "U18") (pin "P$6") (pinfunction "VS_P$6") (pintype "bidirectional"))
      (node (ref "U19") (pin "P$6") (pinfunction "VS_P$6") (pintype "bidirectional"))
      (node (ref "U2") (pin "P$8") (pinfunction "VDD_P$8") (pintype "bidirectional"))
      (node (ref "U8") (pin "P$6") (pinfunction "VS_P$6") (pintype "bidirectional"))
      (node (ref "U9") (pin "P$6") (pinfunction "VS_P$6") (pintype "bidirectional"))
      (node (ref "V12") (pin "P$1") (pinfunction "P$1_P$1") (pintype "bidirectional"))
    )
    (net (code "2") (name "5V") (class "Default")
      (node (ref "T1") (pin "+") (pinfunction "+_+") (pintype "bidirectional"))
      (node (ref "T2") (pin "+") (pinfunction "+_+") (pintype "bidirectional"))
      (node (ref "T3") (pin "+") (pinfunction "+_+") (pintype "bidirectional"))
      (node (ref "T4") (pin "+") (pinfunction "+_+") (pintype "bidirectional"))
      (node (ref "V7") (pin "P$1") (pinfunction "P$1_P$1") (pintype "bidirectional"))
    )
    (net (code "3") (name "GND") (class "Default")
      (node (ref "C1") (pin "2") (pinfunction "P$2_2") (pintype "passive"))
      (node (ref "C11") (pin "2") (pinfunction "P$2_2") (pintype "passive"))
      (node (ref "C12") (pin "2") (pinfunction "P$2_2") (pintype "passive"))
      (node (ref "C13") (pin "1") (pinfunction "P$1_1") (pintype "passive"))
      (node (ref "C14") (pin "1") (pinfunction "P$1_1") (pintype "passive"))
      (node (ref "C15") (pin "1") (pinfunction "P$1_1") (pintype "passive"))
      (node (ref "C16") (pin "1") (pinfunction "P$1_1") (pintype "passive"))
      (node (ref "C17") (pin "2") (pinfunction "P$2_2") (pintype "passive"))
      (node (ref "C18") (pin "2") (pinfunction "P$2_2") (pintype "passive"))
      (node (ref "C2") (pin "2") (pinfunction "P$2_2") (pintype "passive"))
      (node (ref "C21") (pin "2") (pinfunction "P$2_2") (pintype "passive"))
      (node (ref "C22") (pin "2") (pinfunction "P$2_2") (pintype "passive"))
      (node (ref "C23") (pin "2") (pinfunction "P$2_2") (pintype "passive"))
      (node (ref "C24") (pin "2") (pinfunction "P$2_2") (pintype "passive"))
      (node (ref "C25") (pin "1") (pinfunction "P$1_1") (pintype "passive"))
      (node (ref "C26") (pin "1") (pinfunction "P$1_1") (pintype "passive"))
      (node (ref "C28") (pin "2") (pinfunction "P$2_2") (pintype "passive"))
      (node (ref "C29") (pin "1") (pinfunction "P$1_1") (pintype "passive"))
      (node (ref "C3") (pin "2") (pinfunction "P$2_2") (pintype "passive"))
      (node (ref "C30") (pin "2") (pinfunction "P$2_2") (pintype "passive"))
      (node (ref "C31") (pin "2") (pinfunction "P$2_2") (pintype "passive"))
      (node (ref "C32") (pin "1") (pinfunction "P$1_1") (pintype "passive"))
      (node (ref "C33") (pin "1") (pinfunction "P$1_1") (pintype "passive"))
      (node (ref "C35") (pin "2") (pinfunction "P$2_2") (pintype "passive"))
      (node (ref "C36") (pin "1") (pinfunction "P$1_1") (pintype "passive"))
      (node (ref "C37") (pin "2") (pinfunction "P$2_2") (pintype "passive"))
      (node (ref "C38") (pin "2") (pinfunction "P$2_2") (pintype "passive"))
      (node (ref "C4") (pin "2") (pinfunction "P$2_2") (pintype "passive"))
      (node (ref "C5") (pin "2") (pinfunction "P$2_2") (pintype "passive"))
      (node (ref "C6") (pin "2") (pinfunction "P$2_2") (pintype "passive"))
      (node (ref "C7") (pin "2") (pinfunction "P$2_2") (pintype "passive"))
      (node (ref "C8") (pin "2") (pinfunction "P$2_2") (pintype "passive"))
      (node (ref "D4") (pin "A") (pinfunction "A_A") (pintype "passive"))
      (node (ref "D5") (pin "A") (pinfunction "A_A") (pintype "passive"))
      (node (ref "R11") (pin "1") (pinfunction "1_1") (pintype "passive"))
      (node (ref "R14") (pin "1") (pinfunction "1_1") (pintype "passive"))
      (node (ref "R19") (pin "1") (pinfunction "1_1") (pintype "passive"))
      (node (ref "R21") (pin "2") (pinfunction "2_2") (pintype "passive"))
      (node (ref "R23") (pin "1") (pinfunction "1_1") (pintype "passive"))
      (node (ref "R25") (pin "1") (pinfunction "1_1") (pintype "passive"))
      (node (ref "R26") (pin "2") (pinfunction "2_2") (pintype "passive"))
      (node (ref "R28") (pin "1") (pinfunction "1_1") (pintype "passive"))
      (node (ref "R30") (pin "2") (pinfunction "2_2") (pintype "passive"))
      (node (ref "R32") (pin "1") (pinfunction "1_1") (pintype "passive"))
      (node (ref "R34") (pin "1") (pinfunction "1_1") (pintype "passive"))
      (node (ref "R35") (pin "1") (pinfunction "1_1") (pintype "passive"))
      (node (ref "R36") (pin "1") (pinfunction "1_1") (pintype "passive"))
      (node (ref "R40") (pin "1") (pinfunction "1_1") (pintype "passive"))
      (node (ref "R41") (pin "P$1") (pinfunction "1_P$1") (pintype "passive"))
      (node (ref "R44") (pin "1") (pinfunction "1_1") (pintype "passive"))
      (node (ref "R46") (pin "1") (pinfunction "1_1") (pintype "passive"))
      (node (ref "R48") (pin "1") (pinfunction "1_1") (pintype "passive"))
      (node (ref "R50") (pin "1") (pinfunction "1_1") (pintype "passive"))
      (node (ref "R51") (pin "2") (pinfunction "2_2") (pintype "passive"))
      (node (ref "R58") (pin "1") (pinfunction "1_1") (pintype "passive"))
      (node (ref "R59") (pin "P$1") (pinfunction "1_P$1") (pintype "passive"))
      (node (ref "R6") (pin "2") (pinfunction "2_2") (pintype "passive"))
      (node (ref "R62") (pin "1") (pinfunction "1_1") (pintype "passive"))
      (node (ref "R64") (pin "1") (pinfunction "1_1") (pintype "passive"))
      (node (ref "R66") (pin "1") (pinfunction "1_1") (pintype "passive"))
      (node (ref "R68") (pin "1") (pinfunction "1_1") (pintype "passive"))
      (node (ref "R69") (pin "2") (pinfunction "2_2") (pintype "passive"))
      (node (ref "R76") (pin "1") (pinfunction "1_1") (pintype "passive"))
      (node (ref "R77") (pin "1") (pinfunction "1_1") (pintype "passive"))
      (node (ref "R8") (pin "1") (pinfunction "1_1") (pintype "passive"))
      (node (ref "R80") (pin "1") (pinfunction "1_1") (pintype "passive"))
      (node (ref "R9") (pin "1") (pinfunction "1_1") (pintype "passive"))
      (node (ref "SW1") (pin "P$1") (pinfunction "GND_P$1") (pintype "bidirectional"))
      (node (ref "SW2") (pin "P$1") (pinfunction "GND_P$1") (pintype "bidirectional"))
      (node (ref "U1") (pin "P$12") (pinfunction "GND_P$12") (pintype "power_in"))
      (node (ref "U1") (pin "P$2") (pinfunction "A1_P$2") (pintype "bidirectional"))
      (node (ref "U1") (pin "P$21") (pinfunction "A0_P$21") (pintype "bidirectional"))
      (node (ref "U1") (pin "P$3") (pinfunction "A2_P$3") (pintype "bidirectional"))
      (node (ref "U10") (pin "P$4") (pinfunction "GND_P$4") (pintype "bidirectional"))
      (node (ref "U10") (pin "P$6") (pinfunction "NC_P$6") (pintype "bidirectional"))
      (node (ref "U10") (pin "P$7") (pinfunction "NC_P$7") (pintype "bidirectional"))
      (node (ref "U11") (pin "P$4") (pinfunction "GND_P$4") (pintype "bidirectional"))
      (node (ref "U11") (pin "P$6") (pinfunction "NC_P$6") (pintype "bidirectional"))
      (node (ref "U11") (pin "P$7") (pinfunction "NC_P$7") (pintype "bidirectional"))
      (node (ref "U12") (pin "P$2") (pinfunction "GND_P$2") (pintype "bidirectional"))
      (node (ref "U13") (pin "P$2") (pinfunction "GND_P$2") (pintype "bidirectional"))
      (node (ref "U14") (pin "P$12") (pinfunction "NTC_P$12") (pintype "bidirectional"))
      (node (ref "U14") (pin "P$17") (pinfunction "GND_P$17") (pintype "bidirectional"))
      (node (ref "U14") (pin "P$5") (pinfunction "GND_P$5") (pintype "bidirectional"))
      (node (ref "U14") (pin "P$7") (pinfunction "FREQ_P$7") (pintype "bidirectional"))
      (node (ref "U16") (pin "P$12") (pinfunction "NTC_P$12") (pintype "bidirectional"))
      (node (ref "U16") (pin "P$17") (pinfunction "GND_P$17") (pintype "bidirectional"))
      (node (ref "U16") (pin "P$5") (pinfunction "GND_P$5") (pintype "bidirectional"))
      (node (ref "U16") (pin "P$7") (pinfunction "FREQ_P$7") (pintype "bidirectional"))
      (node (ref "U18") (pin "P$1") (pinfunction "-IN_P$1") (pintype "bidirectional"))
      (node (ref "U18") (pin "P$2") (pinfunction "GND_P$2") (pintype "bidirectional"))
      (node (ref "U18") (pin "P$4") (pinfunction "NC_P$4") (pintype "bidirectional"))
      (node (ref "U19") (pin "P$1") (pinfunction "-IN_P$1") (pintype "bidirectional"))
      (node (ref "U19") (pin "P$2") (pinfunction "GND_P$2") (pintype "bidirectional"))
      (node (ref "U19") (pin "P$4") (pinfunction "NC_P$4") (pintype "bidirectional"))
      (node (ref "U2") (pin "P$7") (pinfunction "GND_P$7") (pintype "bidirectional"))
      (node (ref "U3") (pin "P$2") (pinfunction "GND_P$2") (pintype "bidirectional"))
      (node (ref "U3") (pin "P$3") (pinfunction "CNTL_P$3") (pintype "bidirectional"))
      (node (ref "U4") (pin "P$11") (pinfunction "NC_P$11") (pintype "bidirectional"))
      (node (ref "U4") (pin "P$12") (pinfunction "NTC_P$12") (pintype "bidirectional"))
      (node (ref "U4") (pin "P$17") (pinfunction "GND_P$17") (pintype "bidirectional"))
      (node (ref "U4") (pin "P$5") (pinfunction "GND_P$5") (pintype "bidirectional"))
      (node (ref "U4") (pin "P$7") (pinfunction "FREQ_P$7") (pintype "bidirectional"))
      (node (ref "U5") (pin "P$11") (pinfunction "NC_P$11") (pintype "bidirectional"))
      (node (ref "U5") (pin "P$12") (pinfunction "NTC_P$12") (pintype "bidirectional"))
      (node (ref "U5") (pin "P$17") (pinfunction "GND_P$17") (pintype "bidirectional"))
      (node (ref "U5") (pin "P$5") (pinfunction "GND_P$5") (pintype "bidirectional"))
      (node (ref "U5") (pin "P$7") (pinfunction "FREQ_P$7") (pintype "bidirectional"))
      (node (ref "U6") (pin "P$1") (pinfunction "S2_P$1") (pintype "bidirectional"))
      (node (ref "U6") (pin "P$3") (pinfunction "TST_P$3") (pintype "bidirectional"))
      (node (ref "U6") (pin "P$4") (pinfunction "VSS_P$4") (pintype "bidirectional"))
      (node (ref "U7") (pin "P$1") (pinfunction "S2_P$1") (pintype "bidirectional"))
      (node (ref "U7") (pin "P$3") (pinfunction "TST_P$3") (pintype "bidirectional"))
      (node (ref "U7") (pin "P$4") (pinfunction "VSS_P$4") (pintype "bidirectional"))
      (node (ref "U8") (pin "P$2") (pinfunction "GND_P$2") (pintype "bidirectional"))
      (node (ref "U8") (pin "P$4") (pinfunction "NC_P$4") (pintype "bidirectional"))
      (node (ref "U9") (pin "P$2") (pinfunction "GND_P$2") (pintype "bidirectional"))
      (node (ref "U9") (pin "P$4") (pinfunction "NC_P$4") (pintype "bidirectional"))
      (node (ref "V1") (pin "P$1") (pinfunction "P$1_P$1") (pintype "bidirectional"))
      (node (ref "V2") (pin "P$1") (pinfunction "P$1_P$1") (pintype "bidirectional"))
      (node (ref "V28") (pin "P$1") (pinfunction "P$1_P$1") (pintype "bidirectional"))
      (node (ref "V3") (pin "P$1") (pinfunction "P$1_P$1") (pintype "bidirectional"))
      (node (ref "V36") (pin "P$1") (pinfunction "P$1_P$1") (pintype "bidirectional"))
      (node (ref "V4") (pin "P$1") (pinfunction "P$1_P$1") (pintype "bidirectional"))
    )
    (net (code "4") (name "L1_CHG") (class "Default")
      (node (ref "R15") (pin "2") (pinfunction "2_2") (pintype "passive"))
      (node (ref "R35") (pin "2") (pinfunction "2_2") (pintype "passive"))
      (node (ref "U4") (pin "P$16") (pinfunction "RUN_P$16") (pintype "bidirectional"))
      (node (ref "V20") (pin "P$1") (pinfunction "P$1_P$1") (pintype "bidirectional"))
      (node (ref "V48") (pin "P$1") (pinfunction "P$1_P$1") (pintype "bidirectional"))
    )
    (net (code "5") (name "L1_CHGN") (class "Default")
      (node (ref "R17") (pin "1") (pinfunction "1_1") (pintype "passive"))
      (node (ref "U1") (pin "P$8") (pinfunction "P04_P$8") (pintype "bidirectional"))
      (node (ref "U4") (pin "P$14") (pinfunction "~{CHRG}_P$14") (pintype "bidirectional"))
      (node (ref "V27") (pin "P$1") (pinfunction "P$1_P$1") (pintype "bidirectional"))
    )
    (net (code "6") (name "L1_DISG") (class "Default")
      (node (ref "U12") (pin "P$3") (pinfunction "CNTRL_P$3") (pintype "bidirectional"))
      (node (ref "V29") (pin "P$1") (pinfunction "P$1_P$1") (pintype "bidirectional"))
    )
    (net (code "7") (name "L1_FAULTN") (class "Default")
      (node (ref "R18") (pin "1") (pinfunction "1_1") (pintype "passive"))
      (node (ref "U1") (pin "P$9") (pinfunction "P05_P$9") (pintype "bidirectional"))
      (node (ref "U4") (pin "P$15") (pinfunction "~{FAULT}_P$15") (pintype "bidirectional"))
      (node (ref "V26") (pin "P$1") (pinfunction "P$1_P$1") (pintype "bidirectional"))
    )
    (net (code "8") (name "L1_PROG") (class "Default")
      (node (ref "R25") (pin "2") (pinfunction "2_2") (pintype "passive"))
      (node (ref "U4") (pin "P$13") (pinfunction "PROG_P$13") (pintype "bidirectional"))
    )
    (net (code "9") (name "L1_REF") (class "Default")
      (node (ref "R33") (pin "1") (pinfunction "1_1") (pintype "passive"))
      (node (ref "R34") (pin "2") (pinfunction "2_2") (pintype "passive"))
      (node (ref "V21") (pin "P$1") (pinfunction "P$1_P$1") (pintype "bidirectional"))
    )
    (net (code "10") (name "L1_SNS") (class "Default")
      (node (ref "U2") (pin "P$4") (pinfunction "VIN1_P$4") (pintype "bidirectional"))
      (node (ref "U8") (pin "P$5") (pinfunction "OUT_P$5") (pintype "bidirectional"))
    )
    (net (code "11") (name "L1_SNS+") (class "Default")
      (node (ref "LI-ION1") (pin "MINUS") (pinfunction "MINUS_MINUS") (pintype "power_in"))
      (node (ref "R31") (pin "P$2") (pinfunction "2_P$2") (pintype "passive"))
      (node (ref "U8") (pin "P$8") (pinfunction "+IN_P$8") (pintype "bidirectional"))
    )
    (net (code "12") (name "L1_SNS-") (class "Default")
      (node (ref "R31") (pin "P$1") (pinfunction "1_P$1") (pintype "passive"))
      (node (ref "U8") (pin "P$1") (pinfunction "-IN_P$1") (pintype "bidirectional"))
      (node (ref "V22") (pin "P$1") (pinfunction "P$1_P$1") (pintype "bidirectional"))
    )
    (net (code "13") (name "L1_ST") (class "Default")
      (node (ref "R37") (pin "1") (pinfunction "1_1") (pintype "passive"))
      (node (ref "U1") (pin "P$5") (pinfunction "P01_P$5") (pintype "bidirectional"))
      (node (ref "U12") (pin "P$4") (pinfunction "STAT_P$4") (pintype "bidirectional"))
    )
    (net (code "14") (name "L1_TEMP") (class "Default")
      (node (ref "T1") (pin "-") (pinfunction "-_-") (pintype "bidirectional"))
      (node (ref "V8") (pin "P$1") (pinfunction "P$1_P$1") (pintype "bidirectional"))
    )
    (net (code "15") (name "L2_CHG") (class "Default")
      (node (ref "R1") (pin "2") (pinfunction "2_2") (pintype "passive"))
      (node (ref "R36") (pin "2") (pinfunction "2_2") (pintype "passive"))
      (node (ref "U5") (pin "P$16") (pinfunction "RUN_P$16") (pintype "bidirectional"))
      (node (ref "V33") (pin "P$1") (pinfunction "P$1_P$1") (pintype "bidirectional"))
    )
    (net (code "16") (name "L2_CHGN") (class "Default")
      (node (ref "R2") (pin "1") (pinfunction "1_1") (pintype "passive"))
      (node (ref "U1") (pin "P$10") (pinfunction "P06_P$10") (pintype "bidirectional"))
      (node (ref "U5") (pin "P$14") (pinfunction "~{CHRG}_P$14") (pintype "bidirectional"))
    )
    (net (code "17") (name "L2_DISG") (class "Default")
      (node (ref "U13") (pin "P$3") (pinfunction "CNTRL_P$3") (pintype "bidirectional"))
      (node (ref "V30") (pin "P$1") (pinfunction "P$1_P$1") (pintype "bidirectional"))
    )
    (net (code "18") (name "L2_FAULTN") (class "Default")
      (node (ref "R3") (pin "1") (pinfunction "1_1") (pintype "passive"))
      (node (ref "U1") (pin "P$11") (pinfunction "P07_P$11") (pintype "bidirectional"))
      (node (ref "U5") (pin "P$15") (pinfunction "~{FAULT}_P$15") (pintype "bidirectional"))
    )
    (net (code "19") (name "L2_PROG") (class "Default")
      (node (ref "R9") (pin "2") (pinfunction "2_2") (pintype "passive"))
      (node (ref "U5") (pin "P$13") (pinfunction "PROG_P$13") (pintype "bidirectional"))
    )
    (net (code "20") (name "L2_REF") (class "Default")
      (node (ref "R16") (pin "1") (pinfunction "1_1") (pintype "passive"))
      (node (ref "R19") (pin "2") (pinfunction "2_2") (pintype "passive"))
      (node (ref "V31") (pin "P$1") (pinfunction "P$1_P$1") (pintype "bidirectional"))
    )
    (net (code "21") (name "L2_SNS") (class "Default")
      (node (ref "U2") (pin "P$3") (pinfunction "VIN0_P$3") (pintype "bidirectional"))
      (node (ref "U9") (pin "P$5") (pinfunction "OUT_P$5") (pintype "bidirectional"))
    )
    (net (code "22") (name "L2_SNS+") (class "Default")
      (node (ref "LI-ION2") (pin "MINUS") (pinfunction "MINUS_MINUS") (pintype "power_in"))
      (node (ref "R12") (pin "P$2") (pinfunction "2_P$2") (pintype "passive"))
      (node (ref "U9") (pin "P$8") (pinfunction "+IN_P$8") (pintype "bidirectional"))
    )
    (net (code "23") (name "L2_SNS-") (class "Default")
      (node (ref "R12") (pin "P$1") (pinfunction "1_P$1") (pintype "passive"))
      (node (ref "U9") (pin "P$1") (pinfunction "-IN_P$1") (pintype "bidirectional"))
      (node (ref "V24") (pin "P$1") (pinfunction "P$1_P$1") (pintype "bidirectional"))
    )
    (net (code "24") (name "L2_ST") (class "Default")
      (node (ref "R38") (pin "1") (pinfunction "1_1") (pintype "passive"))
      (node (ref "U1") (pin "P$4") (pinfunction "P00_P$4") (pintype "bidirectional"))
      (node (ref "U13") (pin "P$4") (pinfunction "STAT_P$4") (pintype "bidirectional"))
    )
    (net (code "25") (name "L2_TEMP") (class "Default")
      (node (ref "T2") (pin "-") (pinfunction "-_-") (pintype "bidirectional"))
      (node (ref "V9") (pin "P$1") (pinfunction "P$1_P$1") (pintype "bidirectional"))
    )
    (net (code "26") (name "LF1_REF") (class "Default")
      (node (ref "R49") (pin "2") (pinfunction "2_2") (pintype "passive"))
      (node (ref "R50") (pin "2") (pinfunction "2_2") (pintype "passive"))
      (node (ref "V41") (pin "P$1") (pinfunction "P$1_P$1") (pintype "bidirectional"))
    )
    (net (code "27") (name "LF1_TEMP") (class "Default")
      (node (ref "T3") (pin "-") (pinfunction "-_-") (pintype "bidirectional"))
      (node (ref "V10") (pin "P$1") (pinfunction "P$1_P$1") (pintype "bidirectional"))
    )
    (net (code "28") (name "LF2_REF") (class "Default")
      (node (ref "R47") (pin "1") (pinfunction "1_1") (pintype "passive"))
      (node (ref "R48") (pin "2") (pinfunction "2_2") (pintype "passive"))
      (node (ref "V42") (pin "P$1") (pinfunction "P$1_P$1") (pintype "bidirectional"))
    )
    (net (code "29") (name "LF3_REF") (class "Default")
      (node (ref "R67") (pin "2") (pinfunction "2_2") (pintype "passive"))
      (node (ref "R68") (pin "2") (pinfunction "2_2") (pintype "passive"))
      (node (ref "V49") (pin "P$1") (pinfunction "P$1_P$1") (pintype "bidirectional"))
    )
    (net (code "30") (name "LF3_TEMP") (class "Default")
      (node (ref "T4") (pin "-") (pinfunction "-_-") (pintype "bidirectional"))
      (node (ref "V11") (pin "P$1") (pinfunction "P$1_P$1") (pintype "bidirectional"))
    )
    (net (code "31") (name "LF4_REF") (class "Default")
      (node (ref "R65") (pin "1") (pinfunction "1_1") (pintype "passive"))
      (node (ref "R66") (pin "2") (pinfunction "2_2") (pintype "passive"))
      (node (ref "V50") (pin "P$1") (pinfunction "P$1_P$1") (pintype "bidirectional"))
    )
    (net (code "32") (name "LFB1_SNS+") (class "Default")
      (node (ref "LIFEPO42") (pin "MINUS") (pinfunction "MINUS_MINUS") (pintype "power_in"))
      (node (ref "R41") (pin "P$2") (pinfunction "2_P$2") (pintype "passive"))
      (node (ref "U18") (pin "P$8") (pinfunction "+IN_P$8") (pintype "bidirectional"))
    )
    (net (code "33") (name "LFB2_SNS+") (class "Default")
      (node (ref "LIFEPO44") (pin "MINUS") (pinfunction "MINUS_MINUS") (pintype "power_in"))
      (node (ref "R59") (pin "P$2") (pinfunction "2_P$2") (pintype "passive"))
      (node (ref "U19") (pin "P$8") (pinfunction "+IN_P$8") (pintype "bidirectional"))
    )
    (net (code "34") (name "LF_B1") (class "Default")
      (node (ref "C30") (pin "1") (pinfunction "P$1_1") (pintype "passive"))
      (node (ref "SW1") (pin "P$5") (pinfunction "OUT_P$5") (pintype "power_in"))
      (node (ref "SW1") (pin "P$6") (pinfunction "OUT_P$6") (pintype "power_in"))
      (node (ref "SW1") (pin "P$7") (pinfunction "OUT_P$7") (pintype "power_in"))
      (node (ref "V45") (pin "P$1") (pinfunction "P$1_P$1") (pintype "bidirectional"))
    )
    (net (code "35") (name "LF_B1_BT") (class "Default")
      (node (ref "U1") (pin "P$16") (pinfunction "P13_P$16") (pintype "bidirectional"))
    )
    (net (code "36") (name "LF_B1_CHG") (class "Default")
      (node (ref "R44") (pin "2") (pinfunction "2_2") (pintype "passive"))
      (node (ref "U14") (pin "P$16") (pinfunction "RUN_P$16") (pintype "bidirectional"))
      (node (ref "V32") (pin "P$1") (pinfunction "P$1_P$1") (pintype "bidirectional"))
      (node (ref "V35") (pin "P$1") (pinfunction "P$1_P$1") (pintype "bidirectional"))
    )
    (net (code "37") (name "LF_B1_CHGN") (class "Default")
      (node (ref "R42") (pin "1") (pinfunction "1_1") (pintype "passive"))
      (node (ref "U1") (pin "P$20") (pinfunction "P17_P$20") (pintype "bidirectional"))
      (node (ref "U14") (pin "P$14") (pinfunction "~{CHRG}_P$14") (pintype "bidirectional"))
    )
    (net (code "38") (name "LF_B1_FAULTN") (class "Default")
      (node (ref "R43") (pin "1") (pinfunction "1_1") (pintype "passive"))
      (node (ref "U1") (pin "P$19") (pinfunction "P16_P$19") (pintype "bidirectional"))
      (node (ref "U14") (pin "P$15") (pinfunction "~{FAULT}_P$15") (pintype "bidirectional"))
    )
    (net (code "39") (name "LF_B1_OSNS") (class "Default")
      (node (ref "C31") (pin "1") (pinfunction "P$1_1") (pintype "passive"))
      (node (ref "R79") (pin "1") (pinfunction "1_1") (pintype "passive"))
      (node (ref "V46") (pin "P$1") (pinfunction "P$1_P$1") (pintype "bidirectional"))
    )
    (net (code "40") (name "LF_B1_OUTEN") (class "Default")
      (node (ref "R78") (pin "1") (pinfunction "1_1") (pintype "passive"))
      (node (ref "V43") (pin "P$1") (pinfunction "P$1_P$1") (pintype "bidirectional"))
    )
    (net (code "41") (name "LF_B1_SNS") (class "Default")
      (node (ref "U18") (pin "P$5") (pinfunction "OUT_P$5") (pintype "bidirectional"))
      (node (ref "V40") (pin "P$1") (pinfunction "P$1_P$1") (pintype "bidirectional"))
    )
    (net (code "42") (name "LF_B1_TT") (class "Default")
      (node (ref "U1") (pin "P$15") (pinfunction "P12_P$15") (pintype "bidirectional"))
    )
    (net (code "43") (name "LF_B2") (class "Default")
      (node (ref "C37") (pin "1") (pinfunction "P$1_1") (pintype "passive"))
      (node (ref "SW2") (pin "P$5") (pinfunction "OUT_P$5") (pintype "power_in"))
      (node (ref "SW2") (pin "P$6") (pinfunction "OUT_P$6") (pintype "power_in"))
      (node (ref "SW2") (pin "P$7") (pinfunction "OUT_P$7") (pintype "power_in"))
      (node (ref "V53") (pin "P$1") (pinfunction "P$1_P$1") (pintype "bidirectional"))
    )
    (net (code "44") (name "LF_B2_BT") (class "Default")
      (node (ref "U1") (pin "P$13") (pinfunction "P10_P$13") (pintype "bidirectional"))
    )
    (net (code "45") (name "LF_B2_CHG") (class "Default")
      (node (ref "R62") (pin "2") (pinfunction "2_2") (pintype "passive"))
      (node (ref "U16") (pin "P$16") (pinfunction "RUN_P$16") (pintype "bidirectional"))
      (node (ref "V47") (pin "P$1") (pinfunction "P$1_P$1") (pintype "bidirectional"))
    )
    (net (code "46") (name "LF_B2_CHGN") (class "Default")
      (node (ref "R60") (pin "1") (pinfunction "1_1") (pintype "passive"))
      (node (ref "U1") (pin "P$17") (pinfunction "P14_P$17") (pintype "bidirectional"))
      (node (ref "U16") (pin "P$14") (pinfunction "~{CHRG}_P$14") (pintype "bidirectional"))
    )
    (net (code "47") (name "LF_B2_FAULTN") (class "Default")
      (node (ref "R61") (pin "1") (pinfunction "1_1") (pintype "passive"))
      (node (ref "U1") (pin "P$18") (pinfunction "P15_P$18") (pintype "bidirectional"))
      (node (ref "U16") (pin "P$15") (pinfunction "~{FAULT}_P$15") (pintype "bidirectional"))
    )
    (net (code "48") (name "LF_B2_OSNS") (class "Default")
      (node (ref "C38") (pin "1") (pinfunction "P$1_1") (pintype "passive"))
      (node (ref "R82") (pin "1") (pinfunction "1_1") (pintype "passive"))
      (node (ref "V99") (pin "P$1") (pinfunction "P$1_P$1") (pintype "bidirectional"))
    )
    (net (code "49") (name "LF_B2_OUTEN") (class "Default")
      (node (ref "R81") (pin "1") (pinfunction "1_1") (pintype "passive"))
      (node (ref "V51") (pin "P$1") (pinfunction "P$1_P$1") (pintype "bidirectional"))
    )
    (net (code "50") (name "LF_B2_SNS") (class "Default")
      (node (ref "U19") (pin "P$5") (pinfunction "OUT_P$5") (pintype "bidirectional"))
      (node (ref "V44") (pin "P$1") (pinfunction "P$1_P$1") (pintype "bidirectional"))
    )
    (net (code "51") (name "LF_B2_TT") (class "Default")
      (node (ref "U1") (pin "P$14") (pinfunction "P11_P$14") (pintype "bidirectional"))
    )
    (net (code "52") (name "LIFE1") (class "Default")
      (node (ref "C28") (pin "1") (pinfunction "P$1_1") (pintype "passive"))
      (node (ref "D4") (pin "C") (pinfunction "C_C") (pintype "passive"))
      (node (ref "F3") (pin "P$1") (pinfunction "P$1_P$1") (pintype "passive"))
      (node (ref "F4") (pin "P$1") (pinfunction "P$1_P$1") (pintype "passive"))
      (node (ref "LIFEPO41") (pin "PLUS") (pinfunction "PLUS_PLUS") (pintype "power_in"))
      (node (ref "R49") (pin "1") (pinfunction "1_1") (pintype "passive"))
      (node (ref "R53") (pin "2") (pinfunction "2_2") (pintype "passive"))
      (node (ref "U14") (pin "P$9") (pinfunction "BAT_P$9") (pintype "bidirectional"))
    )
    (net (code "53") (name "LIFE1FUSEOUT") (class "Default")
      (node (ref "F3") (pin "P$2") (pinfunction "P$2_P$2") (pintype "passive"))
      (node (ref "F4") (pin "P$2") (pinfunction "P$2_P$2") (pintype "passive"))
      (node (ref "SW1") (pin "PAD") (pinfunction "VB_PAD") (pintype "power_in"))
    )
    (net (code "54") (name "LIFE3") (class "Default")
      (node (ref "C35") (pin "1") (pinfunction "P$1_1") (pintype "passive"))
      (node (ref "D5") (pin "C") (pinfunction "C_C") (pintype "passive"))
      (node (ref "F5") (pin "P$1") (pinfunction "P$1_P$1") (pintype "passive"))
      (node (ref "F6") (pin "P$1") (pinfunction "P$1_P$1") (pintype "passive"))
      (node (ref "LIFEPO43") (pin "PLUS") (pinfunction "PLUS_PLUS") (pintype "power_in"))
      (node (ref "R67") (pin "1") (pinfunction "1_1") (pintype "passive"))
      (node (ref "R71") (pin "2") (pinfunction "2_2") (pintype "passive"))
      (node (ref "U16") (pin "P$9") (pinfunction "BAT_P$9") (pintype "bidirectional"))
    )
    (net (code "55") (name "LIFE3FUSEOUT") (class "Default")
      (node (ref "F5") (pin "P$2") (pinfunction "P$2_P$2") (pintype "passive"))
      (node (ref "F6") (pin "P$2") (pinfunction "P$2_P$2") (pintype "passive"))
      (node (ref "SW2") (pin "PAD") (pinfunction "VB_PAD") (pintype "power_in"))
    )
    (net (code "56") (name "LION1") (class "Default")
      (node (ref "C11") (pin "1") (pinfunction "P$1_1") (pintype "passive"))
      (node (ref "F1") (pin "1") (pinfunction "P$1_1") (pintype "passive"))
      (node (ref "LI-ION1") (pin "PLUS") (pinfunction "PLUS_PLUS") (pintype "power_in"))
      (node (ref "R33") (pin "2") (pinfunction "2_2") (pintype "passive"))
      (node (ref "R7") (pin "2") (pinfunction "2_2") (pintype "passive"))
      (node (ref "U4") (pin "P$10") (pinfunction "BATSNS_P$10") (pintype "bidirectional"))
      (node (ref "U4") (pin "P$9") (pinfunction "BAT_P$9") (pintype "bidirectional"))
    )
    (net (code "57") (name "LION1_OUT") (class "Default")
      (node (ref "C15") (pin "2") (pinfunction "P$2_2") (pintype "passive"))
      (node (ref "F1") (pin "2") (pinfunction "P$2_2") (pintype "passive"))
      (node (ref "U12") (pin "P$1") (pinfunction "IN_P$1") (pintype "bidirectional"))
    )
    (net (code "58") (name "LION2") (class "Default")
      (node (ref "C12") (pin "1") (pinfunction "P$1_1") (pintype "passive"))
      (node (ref "F2") (pin "1") (pinfunction "P$1_1") (pintype "passive"))
      (node (ref "LI-ION2") (pin "PLUS") (pinfunction "PLUS_PLUS") (pintype "power_in"))
      (node (ref "R16") (pin "2") (pinfunction "2_2") (pintype "passive"))
      (node (ref "R22") (pin "2") (pinfunction "2_2") (pintype "passive"))
      (node (ref "U5") (pin "P$10") (pinfunction "BATSNS_P$10") (pintype "bidirectional"))
      (node (ref "U5") (pin "P$9") (pinfunction "BAT_P$9") (pintype "bidirectional"))
    )
    (net (code "59") (name "LION2_OUT") (class "Default")
      (node (ref "C16") (pin "2") (pinfunction "P$2_2") (pintype "passive"))
      (node (ref "F2") (pin "2") (pinfunction "P$2_2") (pintype "passive"))
      (node (ref "U13") (pin "P$1") (pinfunction "IN_P$1") (pintype "bidirectional"))
    )
    (net (code "60") (name "L_OUT") (class "Default")
      (node (ref "C21") (pin "1") (pinfunction "P$1_1") (pintype "passive"))
      (node (ref "C22") (pin "1") (pinfunction "P$1_1") (pintype "passive"))
      (node (ref "D2") (pin "C") (pinfunction "C_C") (pintype "bidirectional"))
      (node (ref "D3") (pin "C") (pinfunction "C_C") (pintype "bidirectional"))
      (node (ref "R37") (pin "2") (pinfunction "2_2") (pintype "passive"))
      (node (ref "R38") (pin "2") (pinfunction "2_2") (pintype "passive"))
      (node (ref "R39") (pin "2") (pinfunction "2_2") (pintype "passive"))
      (node (ref "U12") (pin "P$5") (pinfunction "OUT_P$5") (pintype "bidirectional"))
      (node (ref "U13") (pin "P$5") (pinfunction "OUT_P$5") (pintype "bidirectional"))
      (node (ref "V34") (pin "P$1") (pinfunction "P$1_P$1") (pintype "bidirectional"))
    )
    (net (code "61") (name "L_REF") (class "Default")
      (node (ref "R39") (pin "1") (pinfunction "1_1") (pintype "passive"))
      (node (ref "R40") (pin "2") (pinfunction "2_2") (pintype "passive"))
      (node (ref "U2") (pin "P$5") (pinfunction "VIN2_P$5") (pintype "bidirectional"))
    )
    (net (code "62") (name "Net-(C7-P$1)") (class "Default")
      (node (ref "C7") (pin "1") (pinfunction "P$1_1") (pintype "passive"))
      (node (ref "U4") (pin "P$1") (pinfunction "INTVCC_P$1") (pintype "bidirectional"))
    )
    (net (code "63") (name "Net-(C8-P$1)") (class "Default")
      (node (ref "C8") (pin "1") (pinfunction "P$1_1") (pintype "passive"))
      (node (ref "U5") (pin "P$1") (pinfunction "INTVCC_P$1") (pintype "bidirectional"))
    )
    (net (code "64") (name "Net-(C9-P$1)") (class "Default")
      (node (ref "C9") (pin "1") (pinfunction "P$1_1") (pintype "passive"))
      (node (ref "U4") (pin "P$2") (pinfunction "BOOST_P$2") (pintype "bidirectional"))
    )
    (net (code "65") (name "Net-(C9-P$2)") (class "Default")
      (node (ref "C9") (pin "2") (pinfunction "P$2_2") (pintype "passive"))
      (node (ref "L1") (pin "P$1") (pinfunction "P$1_P$1") (pintype "passive"))
      (node (ref "U4") (pin "P$4") (pinfunction "SW_P$4") (pintype "bidirectional"))
    )
    (net (code "66") (name "Net-(C10-P$1)") (class "Default")
      (node (ref "C10") (pin "1") (pinfunction "P$1_1") (pintype "passive"))
      (node (ref "U5") (pin "P$2") (pinfunction "BOOST_P$2") (pintype "bidirectional"))
    )
    (net (code "67") (name "Net-(C10-P$2)") (class "Default")
      (node (ref "C10") (pin "2") (pinfunction "P$2_2") (pintype "passive"))
      (node (ref "L2") (pin "P$1") (pinfunction "P$1_P$1") (pintype "passive"))
      (node (ref "U5") (pin "P$4") (pinfunction "SW_P$4") (pintype "bidirectional"))
    )
    (net (code "68") (name "Net-(C13-P$2)") (class "Default")
      (node (ref "C13") (pin "2") (pinfunction "P$2_2") (pintype "passive"))
      (node (ref "R7") (pin "1") (pinfunction "1_1") (pintype "passive"))
      (node (ref "U6") (pin "P$5") (pinfunction "VCC_P$5") (pintype "bidirectional"))
    )
    (net (code "69") (name "Net-(C14-P$2)") (class "Default")
      (node (ref "C14") (pin "2") (pinfunction "P$2_2") (pintype "passive"))
      (node (ref "R22") (pin "1") (pinfunction "1_1") (pintype "passive"))
      (node (ref "U7") (pin "P$5") (pinfunction "VCC_P$5") (pintype "bidirectional"))
    )
    (net (code "70") (name "Net-(C19-P$1)") (class "Default")
      (node (ref "C19") (pin "1") (pinfunction "P$1_1") (pintype "passive"))
      (node (ref "C23") (pin "1") (pinfunction "P$1_1") (pintype "passive"))
      (node (ref "D2") (pin "A") (pinfunction "A_A") (pintype "bidirectional"))
      (node (ref "U10") (pin "P$1") (pinfunction "OUT_P$1") (pintype "bidirectional"))
      (node (ref "U10") (pin "P$2") (pinfunction "SENSE_P$2") (pintype "bidirectional"))
    )
    (net (code "71") (name "Net-(C19-P$2)") (class "Default")
      (node (ref "C19") (pin "2") (pinfunction "P$2_2") (pintype "passive"))
      (node (ref "U10") (pin "P$3") (pinfunction "BYP_P$3") (pintype "bidirectional"))
    )
    (net (code "72") (name "Net-(C20-P$1)") (class "Default")
      (node (ref "C20") (pin "1") (pinfunction "P$1_1") (pintype "passive"))
      (node (ref "C24") (pin "1") (pinfunction "P$1_1") (pintype "passive"))
      (node (ref "D3") (pin "A") (pinfunction "A_A") (pintype "bidirectional"))
      (node (ref "U11") (pin "P$1") (pinfunction "OUT_P$1") (pintype "bidirectional"))
      (node (ref "U11") (pin "P$2") (pinfunction "SENSE_P$2") (pintype "bidirectional"))
    )
    (net (code "73") (name "Net-(C20-P$2)") (class "Default")
      (node (ref "C20") (pin "2") (pinfunction "P$2_2") (pintype "passive"))
      (node (ref "U11") (pin "P$3") (pinfunction "BYP_P$3") (pintype "bidirectional"))
    )
    (net (code "74") (name "Net-(C26-P$2)") (class "Default")
      (node (ref "C26") (pin "2") (pinfunction "P$2_2") (pintype "passive"))
      (node (ref "U14") (pin "P$1") (pinfunction "INTVCC_P$1") (pintype "bidirectional"))
    )
    (net (code "75") (name "Net-(C27-P$1)") (class "Default")
      (node (ref "C27") (pin "1") (pinfunction "P$1_1") (pintype "passive"))
      (node (ref "L3") (pin "P$2") (pinfunction "P$2_P$2") (pintype "passive"))
      (node (ref "U14") (pin "P$4") (pinfunction "SW_P$4") (pintype "bidirectional"))
    )
    (net (code "76") (name "Net-(C27-P$2)") (class "Default")
      (node (ref "C27") (pin "2") (pinfunction "P$2_2") (pintype "passive"))
      (node (ref "U14") (pin "P$2") (pinfunction "BOOST_P$2") (pintype "bidirectional"))
    )
    (net (code "77") (name "Net-(C29-P$2)") (class "Default")
      (node (ref "C29") (pin "2") (pinfunction "P$2_2") (pintype "passive"))
      (node (ref "R77") (pin "2") (pinfunction "2_2") (pintype "passive"))
      (node (ref "R78") (pin "2") (pinfunction "2_2") (pintype "passive"))
      (node (ref "SW1") (pin "P$2") (pinfunction "CNTRL_P$2") (pintype "input"))
    )
    (net (code "78") (name "Net-(C33-P$2)") (class "Default")
      (node (ref "C33") (pin "2") (pinfunction "P$2_2") (pintype "passive"))
      (node (ref "U16") (pin "P$1") (pinfunction "INTVCC_P$1") (pintype "bidirectional"))
    )
    (net (code "79") (name "Net-(C34-P$1)") (class "Default")
      (node (ref "C34") (pin "1") (pinfunction "P$1_1") (pintype "passive"))
      (node (ref "L4") (pin "P$2") (pinfunction "P$2_P$2") (pintype "passive"))
      (node (ref "U16") (pin "P$4") (pinfunction "SW_P$4") (pintype "bidirectional"))
    )
    (net (code "80") (name "Net-(C34-P$2)") (class "Default")
      (node (ref "C34") (pin "2") (pinfunction "P$2_2") (pintype "passive"))
      (node (ref "U16") (pin "P$2") (pinfunction "BOOST_P$2") (pintype "bidirectional"))
    )
    (net (code "81") (name "Net-(C36-P$2)") (class "Default")
      (node (ref "C36") (pin "2") (pinfunction "P$2_2") (pintype "passive"))
      (node (ref "R80") (pin "2") (pinfunction "2_2") (pintype "passive"))
      (node (ref "R81") (pin "2") (pinfunction "2_2") (pintype "passive"))
      (node (ref "SW2") (pin "P$2") (pinfunction "CNTRL_P$2") (pintype "input"))
    )
    (net (code "82") (name "Net-(LIFEPO41-PadMINUS)") (class "Default")
      (node (ref "LIFEPO41") (pin "MINUS") (pinfunction "MINUS_MINUS") (pintype "power_in"))
      (node (ref "LIFEPO42") (pin "PLUS") (pinfunction "PLUS_PLUS") (pintype "power_in"))
      (node (ref "R47") (pin "2") (pinfunction "2_2") (pintype "passive"))
    )
    (net (code "83") (name "Net-(LIFEPO43-PadMINUS)") (class "Default")
      (node (ref "LIFEPO43") (pin "MINUS") (pinfunction "MINUS_MINUS") (pintype "power_in"))
      (node (ref "LIFEPO44") (pin "PLUS") (pinfunction "PLUS_PLUS") (pintype "power_in"))
      (node (ref "R65") (pin "2") (pinfunction "2_2") (pintype "passive"))
    )
    (net (code "84") (name "Net-(M1-G)") (class "Default")
      (node (ref "M1") (pin "P$4") (pinfunction "G_P$4") (pintype "bidirectional"))
      (node (ref "U3") (pin "P$5") (pinfunction "GATE_P$5") (pintype "bidirectional"))
    )
    (net (code "85") (name "Net-(SW1-ISNS)") (class "Default")
      (node (ref "R58") (pin "2") (pinfunction "2_2") (pintype "passive"))
      (node (ref "R79") (pin "2") (pinfunction "2_2") (pintype "passive"))
      (node (ref "SW1") (pin "P$3") (pinfunction "ISNS_P$3") (pintype "output"))
    )
    (net (code "86") (name "Net-(SW2-ISNS)") (class "Default")
      (node (ref "R76") (pin "2") (pinfunction "2_2") (pintype "passive"))
      (node (ref "R82") (pin "2") (pinfunction "2_2") (pintype "passive"))
      (node (ref "SW2") (pin "P$3") (pinfunction "ISNS_P$3") (pintype "output"))
    )
    (net (code "87") (name "Net-(U1-P03)") (class "Default")
      (node (ref "R32") (pin "2") (pinfunction "2_2") (pintype "passive"))
      (node (ref "U1") (pin "P$7") (pinfunction "P03_P$7") (pintype "bidirectional"))
    )
    (net (code "88") (name "Net-(U4-CHGSNS)") (class "Default")
      (node (ref "L1") (pin "P$2") (pinfunction "P$2_P$2") (pintype "passive"))
      (node (ref "U4") (pin "P$8") (pinfunction "CHGSNS_P$8") (pintype "bidirectional"))
    )
    (net (code "89") (name "Net-(U4-MPPT)") (class "Default")
      (node (ref "R27") (pin "1") (pinfunction "1_1") (pintype "passive"))
      (node (ref "R28") (pin "2") (pinfunction "2_2") (pintype "passive"))
      (node (ref "U4") (pin "P$6") (pinfunction "MPPT_P$6") (pintype "bidirectional"))
    )
    (net (code "90") (name "Net-(U5-CHGSNS)") (class "Default")
      (node (ref "L2") (pin "P$2") (pinfunction "P$2_P$2") (pintype "passive"))
      (node (ref "U5") (pin "P$8") (pinfunction "CHGSNS_P$8") (pintype "bidirectional"))
    )
    (net (code "91") (name "Net-(U5-MPPT)") (class "Default")
      (node (ref "R10") (pin "1") (pinfunction "1_1") (pintype "passive"))
      (node (ref "R11") (pin "2") (pinfunction "2_2") (pintype "passive"))
      (node (ref "U5") (pin "P$6") (pinfunction "MPPT_P$6") (pintype "bidirectional"))
    )
    (net (code "92") (name "Net-(U6-CS)") (class "Default")
      (node (ref "R8") (pin "2") (pinfunction "2_2") (pintype "passive"))
      (node (ref "U6") (pin "P$2") (pinfunction "CS_P$2") (pintype "bidirectional"))
    )
    (net (code "93") (name "Net-(U6-S1)") (class "Default")
      (node (ref "U6") (pin "P$6") (pinfunction "S1_P$6") (pintype "bidirectional"))
      (node (ref "V23") (pin "P$1") (pinfunction "P$1_P$1") (pintype "bidirectional"))
    )
    (net (code "94") (name "Net-(U7-CS)") (class "Default")
      (node (ref "R23") (pin "2") (pinfunction "2_2") (pintype "passive"))
      (node (ref "U7") (pin "P$2") (pinfunction "CS_P$2") (pintype "bidirectional"))
    )
    (net (code "95") (name "Net-(U7-S1)") (class "Default")
      (node (ref "U7") (pin "P$6") (pinfunction "S1_P$6") (pintype "bidirectional"))
      (node (ref "V25") (pin "P$1") (pinfunction "P$1_P$1") (pintype "bidirectional"))
    )
    (net (code "96") (name "Net-(U8-VREF1)") (class "Default")
      (node (ref "R4") (pin "2") (pinfunction "2_2") (pintype "passive"))
      (node (ref "R6") (pin "1") (pinfunction "1_1") (pintype "passive"))
      (node (ref "U8") (pin "P$3") (pinfunction "VREF2_P$3") (pintype "bidirectional"))
      (node (ref "U8") (pin "P$7") (pinfunction "VREF1_P$7") (pintype "bidirectional"))
    )
    (net (code "97") (name "Net-(U9-VREF1)") (class "Default")
      (node (ref "R20") (pin "2") (pinfunction "2_2") (pintype "passive"))
      (node (ref "R21") (pin "1") (pinfunction "1_1") (pintype "passive"))
      (node (ref "U9") (pin "P$3") (pinfunction "VREF2_P$3") (pintype "bidirectional"))
      (node (ref "U9") (pin "P$7") (pinfunction "VREF1_P$7") (pintype "bidirectional"))
    )
    (net (code "98") (name "Net-(U14-CHGSNS)") (class "Default")
      (node (ref "L3") (pin "P$1") (pinfunction "P$1_P$1") (pintype "passive"))
      (node (ref "U14") (pin "P$8") (pinfunction "CHGSNS_P$8") (pintype "bidirectional"))
    )
    (net (code "99") (name "Net-(U14-FB)") (class "Default")
      (node (ref "R52") (pin "2") (pinfunction "2_2") (pintype "passive"))
      (node (ref "R53") (pin "1") (pinfunction "1_1") (pintype "passive"))
      (node (ref "U14") (pin "P$10") (pinfunction "FB_P$10") (pintype "bidirectional"))
    )
    (net (code "100") (name "Net-(U14-FBG)") (class "Default")
      (node (ref "R52") (pin "1") (pinfunction "1_1") (pintype "passive"))
      (node (ref "U14") (pin "P$11") (pinfunction "FBG_P$11") (pintype "bidirectional"))
    )
    (net (code "101") (name "Net-(U14-MPPT)") (class "Default")
      (node (ref "R45") (pin "1") (pinfunction "1_1") (pintype "passive"))
      (node (ref "R46") (pin "2") (pinfunction "2_2") (pintype "passive"))
      (node (ref "U14") (pin "P$6") (pinfunction "MPPT_P$6") (pintype "bidirectional"))
    )
    (net (code "102") (name "Net-(U14-PROG)") (class "Default")
      (node (ref "R51") (pin "1") (pinfunction "1_1") (pintype "passive"))
      (node (ref "U14") (pin "P$13") (pinfunction "PROG_P$13") (pintype "bidirectional"))
    )
    (net (code "103") (name "Net-(U16-CHGSNS)") (class "Default")
      (node (ref "L4") (pin "P$1") (pinfunction "P$1_P$1") (pintype "passive"))
      (node (ref "U16") (pin "P$8") (pinfunction "CHGSNS_P$8") (pintype "bidirectional"))
    )
    (net (code "104") (name "Net-(U16-FB)") (class "Default")
      (node (ref "R70") (pin "2") (pinfunction "2_2") (pintype "passive"))
      (node (ref "R71") (pin "1") (pinfunction "1_1") (pintype "passive"))
      (node (ref "U16") (pin "P$10") (pinfunction "FB_P$10") (pintype "bidirectional"))
    )
    (net (code "105") (name "Net-(U16-FBG)") (class "Default")
      (node (ref "R70") (pin "1") (pinfunction "1_1") (pintype "passive"))
      (node (ref "U16") (pin "P$11") (pinfunction "FBG_P$11") (pintype "bidirectional"))
    )
    (net (code "106") (name "Net-(U16-MPPT)") (class "Default")
      (node (ref "R63") (pin "1") (pinfunction "1_1") (pintype "passive"))
      (node (ref "R64") (pin "2") (pinfunction "2_2") (pintype "passive"))
      (node (ref "U16") (pin "P$6") (pinfunction "MPPT_P$6") (pintype "bidirectional"))
    )
    (net (code "107") (name "Net-(U16-PROG)") (class "Default")
      (node (ref "R69") (pin "1") (pinfunction "1_1") (pintype "passive"))
      (node (ref "U16") (pin "P$13") (pinfunction "PROG_P$13") (pintype "bidirectional"))
    )
    (net (code "108") (name "Net-(U18-VREF1)") (class "Default")
      (node (ref "R24") (pin "2") (pinfunction "2_2") (pintype "passive"))
      (node (ref "R26") (pin "1") (pinfunction "1_1") (pintype "passive"))
      (node (ref "U18") (pin "P$3") (pinfunction "VREF2_P$3") (pintype "bidirectional"))
      (node (ref "U18") (pin "P$7") (pinfunction "VREF1_P$7") (pintype "bidirectional"))
    )
    (net (code "109") (name "Net-(U19-VREF1)") (class "Default")
      (node (ref "R29") (pin "2") (pinfunction "2_2") (pintype "passive"))
      (node (ref "R30") (pin "1") (pinfunction "1_1") (pintype "passive"))
      (node (ref "U19") (pin "P$3") (pinfunction "VREF2_P$3") (pintype "bidirectional"))
      (node (ref "U19") (pin "P$7") (pinfunction "VREF1_P$7") (pintype "bidirectional"))
    )
    (net (code "110") (name "PANELREF") (class "Default")
      (node (ref "R13") (pin "1") (pinfunction "1_1") (pintype "passive"))
      (node (ref "R14") (pin "2") (pinfunction "2_2") (pintype "passive"))
      (node (ref "U2") (pin "P$6") (pinfunction "VIN3/REF_P$6") (pintype "bidirectional"))
    )
    (net (code "111") (name "SCL") (class "Default")
      (node (ref "R85") (pin "1") (pinfunction "1_1") (pintype "passive"))
      (node (ref "U1") (pin "P$22") (pinfunction "SCL_P$22") (pintype "bidirectional"))
      (node (ref "U2") (pin "P$1") (pinfunction "SCL_P$1") (pintype "bidirectional"))
      (node (ref "V5") (pin "P$1") (pinfunction "P$1_P$1") (pintype "bidirectional"))
    )
    (net (code "112") (name "SDA") (class "Default")
      (node (ref "R86") (pin "1") (pinfunction "1_1") (pintype "passive"))
      (node (ref "U1") (pin "P$23") (pinfunction "SDA_P$23") (pintype "bidirectional"))
      (node (ref "U2") (pin "P$2") (pinfunction "SDA_P$2") (pintype "bidirectional"))
      (node (ref "V6") (pin "P$1") (pinfunction "P$1_P$1") (pintype "bidirectional"))
    )
    (net (code "113") (name "SPF_ST") (class "Default")
      (node (ref "R83") (pin "1") (pinfunction "1_1") (pintype "passive"))
      (node (ref "U1") (pin "P$6") (pinfunction "P02_P$6") (pintype "bidirectional"))
      (node (ref "U3") (pin "P$4") (pinfunction "STAT_P$4") (pintype "bidirectional"))
    )
    (net (code "114") (name "SP_C") (class "Default")
      (node (ref "C3") (pin "1") (pinfunction "P$1_1") (pintype "passive"))
      (node (ref "M1") (pin "P$5") (pinfunction "D_P$5") (pintype "bidirectional"))
      (node (ref "M1") (pin "P$6") (pinfunction "D_P$6") (pintype "bidirectional"))
      (node (ref "M1") (pin "P$7") (pinfunction "D_P$7") (pintype "bidirectional"))
      (node (ref "M1") (pin "P$8") (pinfunction "D_P$8") (pintype "bidirectional"))
      (node (ref "U3") (pin "P$1") (pinfunction "VIN_P$1") (pintype "bidirectional"))
      (node (ref "V13") (pin "P$1") (pinfunction "P$1_P$1") (pintype "bidirectional"))
      (node (ref "V14") (pin "P$1") (pinfunction "P$1_P$1") (pintype "bidirectional"))
      (node (ref "V15") (pin "P$1") (pinfunction "P$1_P$1") (pintype "bidirectional"))
      (node (ref "V16") (pin "P$1") (pinfunction "P$1_P$1") (pintype "bidirectional"))
      (node (ref "V17") (pin "P$1") (pinfunction "P$1_P$1") (pintype "bidirectional"))
      (node (ref "V18") (pin "P$1") (pinfunction "P$1_P$1") (pintype "bidirectional"))
    )
    (net (code "115") (name "SP_OUT") (class "Default")
      (node (ref "C17") (pin "1") (pinfunction "P$1_1") (pintype "passive"))
      (node (ref "C18") (pin "1") (pinfunction "P$1_1") (pintype "passive"))
      (node (ref "C25") (pin "2") (pinfunction "P$2_2") (pintype "passive"))
      (node (ref "C32") (pin "2") (pinfunction "P$2_2") (pintype "passive"))
      (node (ref "C4") (pin "1") (pinfunction "P$1_1") (pintype "passive"))
      (node (ref "C5") (pin "1") (pinfunction "P$1_1") (pintype "passive"))
      (node (ref "C6") (pin "1") (pinfunction "P$1_1") (pintype "passive"))
      (node (ref "D1") (pin "C") (pinfunction "C_C") (pintype "bidirectional"))
      (node (ref "M1") (pin "P$1") (pinfunction "S_P$1") (pintype "bidirectional"))
      (node (ref "M1") (pin "P$2") (pinfunction "S_P$2") (pintype "bidirectional"))
      (node (ref "M1") (pin "P$3") (pinfunction "S_P$3") (pintype "bidirectional"))
      (node (ref "R1") (pin "1") (pinfunction "1_1") (pintype "passive"))
      (node (ref "R10") (pin "2") (pinfunction "2_2") (pintype "passive"))
      (node (ref "R13") (pin "2") (pinfunction "2_2") (pintype "passive"))
      (node (ref "R15") (pin "1") (pinfunction "1_1") (pintype "passive"))
      (node (ref "R27") (pin "2") (pinfunction "2_2") (pintype "passive"))
      (node (ref "R45") (pin "2") (pinfunction "2_2") (pintype "passive"))
      (node (ref "R63") (pin "2") (pinfunction "2_2") (pintype "passive"))
      (node (ref "U10") (pin "P$5") (pinfunction "~{SHDN}_P$5") (pintype "bidirectional"))
      (node (ref "U10") (pin "P$8") (pinfunction "IN_P$8") (pintype "bidirectional"))
      (node (ref "U11") (pin "P$5") (pinfunction "~{SHDN}_P$5") (pintype "bidirectional"))
      (node (ref "U11") (pin "P$8") (pinfunction "IN_P$8") (pintype "bidirectional"))
      (node (ref "U14") (pin "P$3") (pinfunction "IN_P$3") (pintype "bidirectional"))
      (node (ref "U16") (pin "P$3") (pinfunction "IN_P$3") (pintype "bidirectional"))
      (node (ref "U3") (pin "P$6") (pinfunction "SNS_P$6") (pintype "bidirectional"))
      (node (ref "U4") (pin "P$3") (pinfunction "IN_P$3") (pintype "bidirectional"))
      (node (ref "U5") (pin "P$3") (pinfunction "IN_P$3") (pintype "bidirectional"))
    )
    (net (code "116") (name "UMB_CHG") (class "Default")
      (node (ref "D1") (pin "A") (pinfunction "A_A") (pintype "bidirectional"))
      (node (ref "V19") (pin "P$1") (pinfunction "P$1_P$1") (pintype "bidirectional"))
    )
    (net (code "117") (name "~{BATT_INT}") (class "Default")
      (node (ref "R84") (pin "1") (pinfunction "1_1") (pintype "passive"))
      (node (ref "U1") (pin "P$1") (pinfunction "~{INT}_P$1") (pintype "bidirectional"))
    )
  )
)
